# LARIX_V2.net
KiCad netlist of a schematic drawn in EAGLE
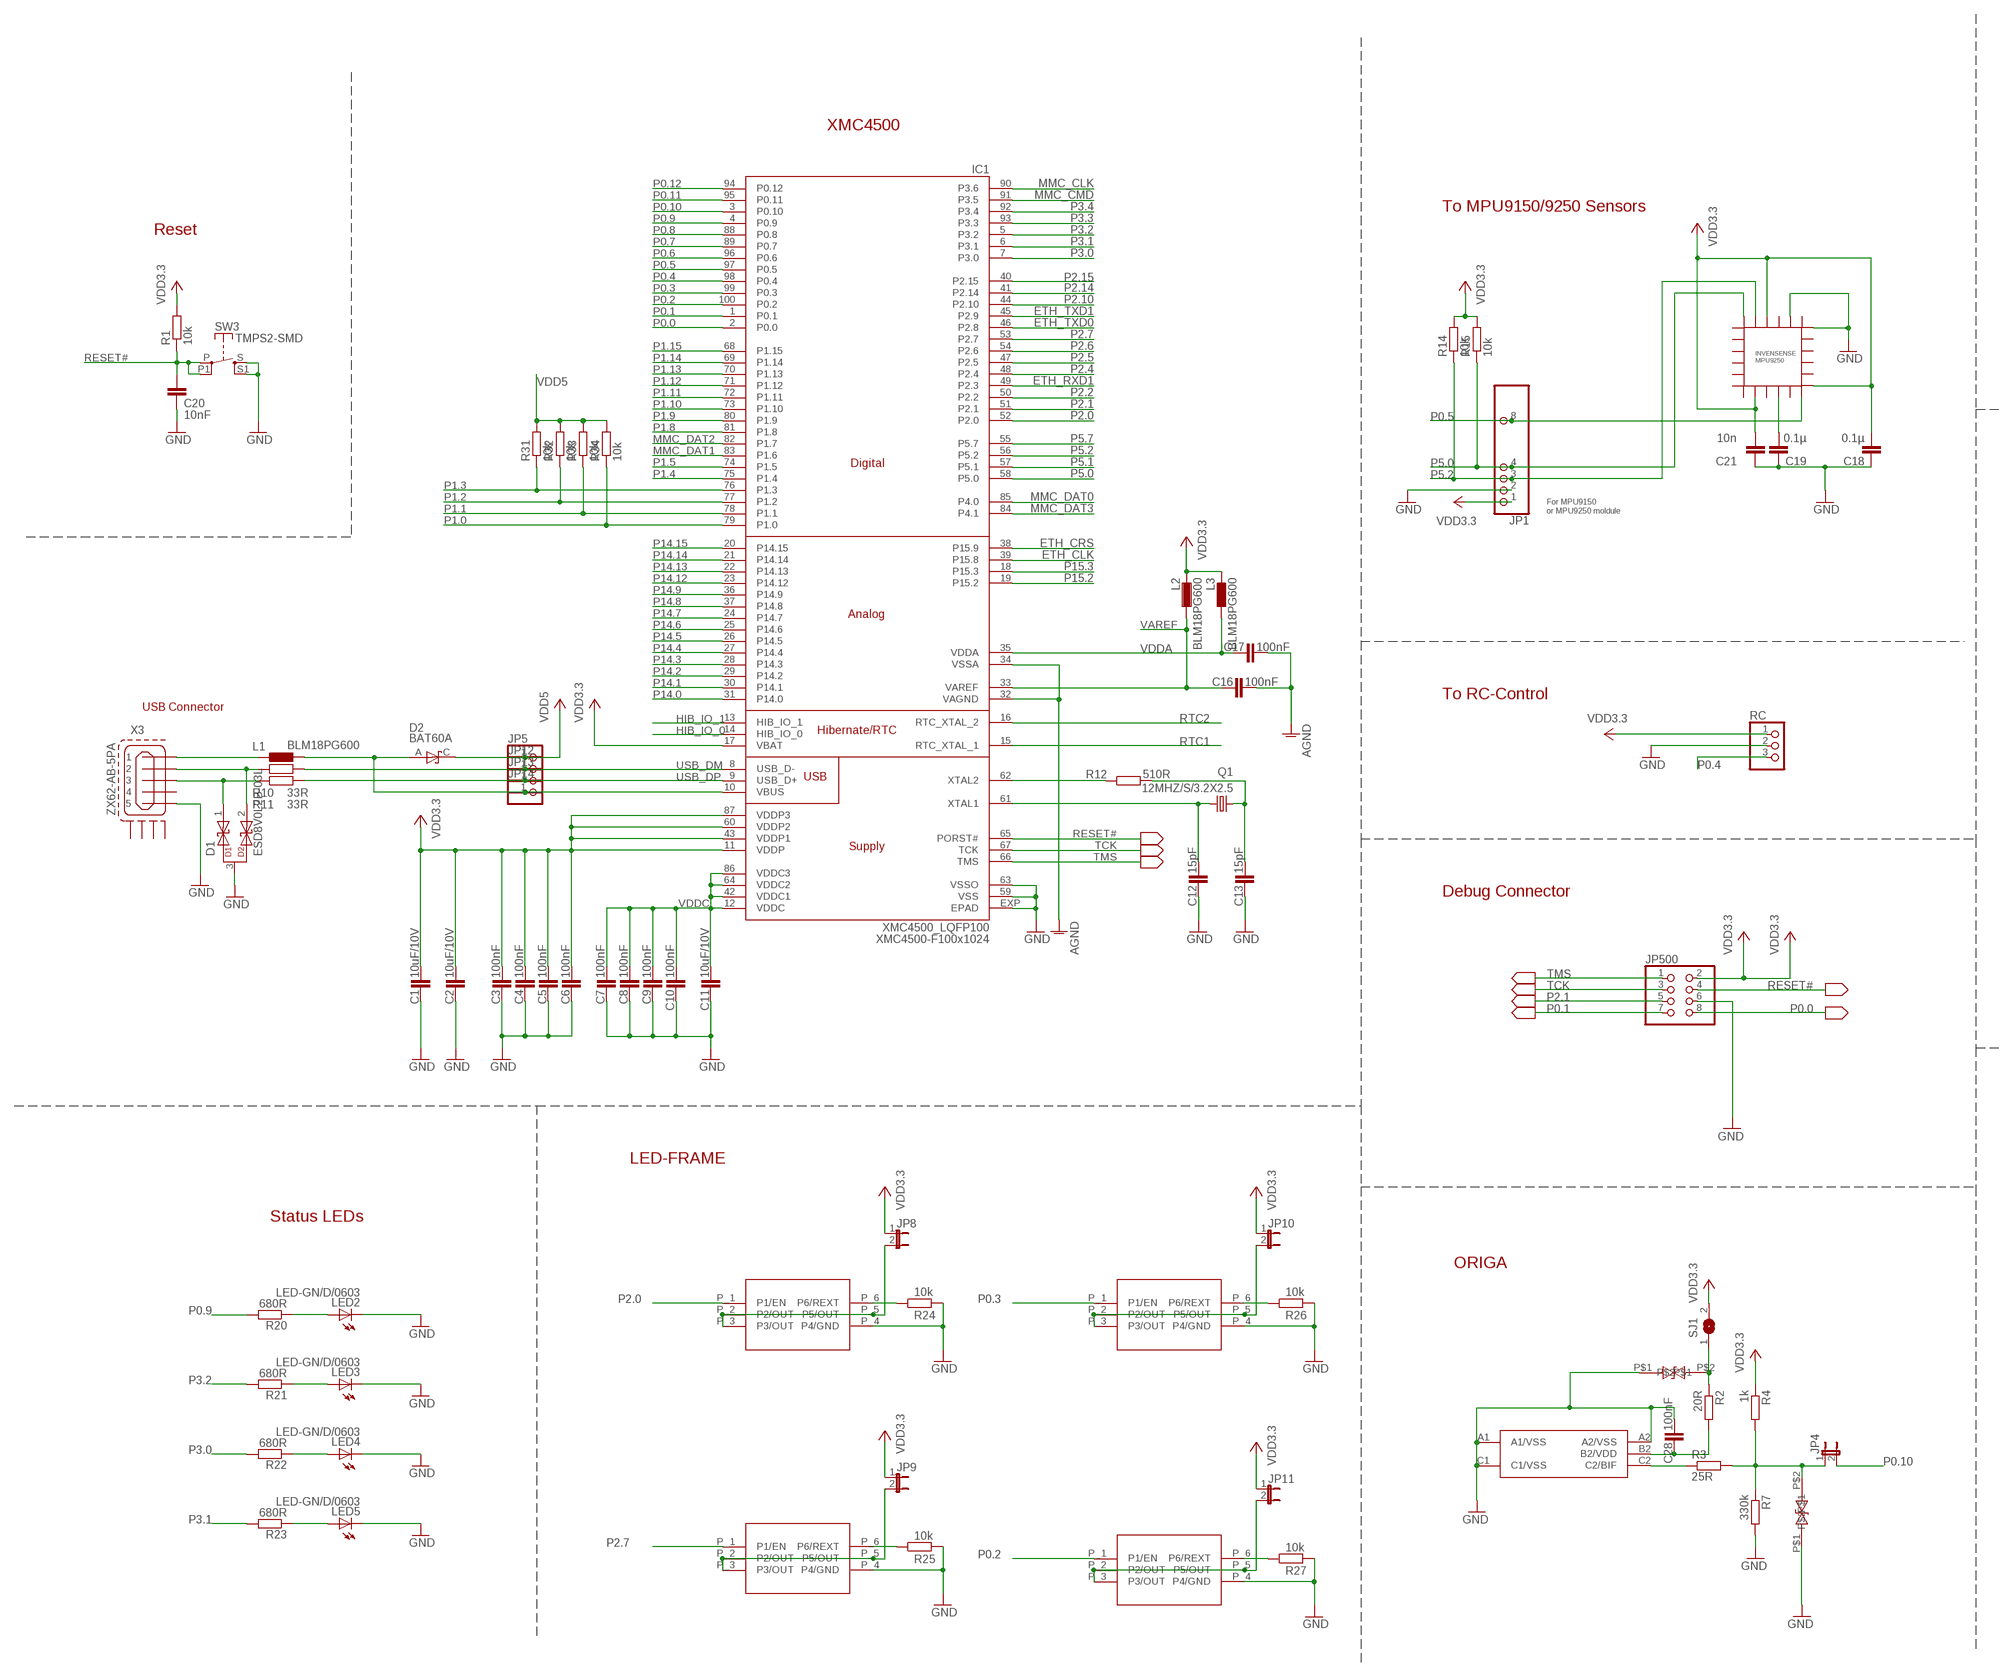
[diagram p0: schematic, sheet 1, part 1 of 2]
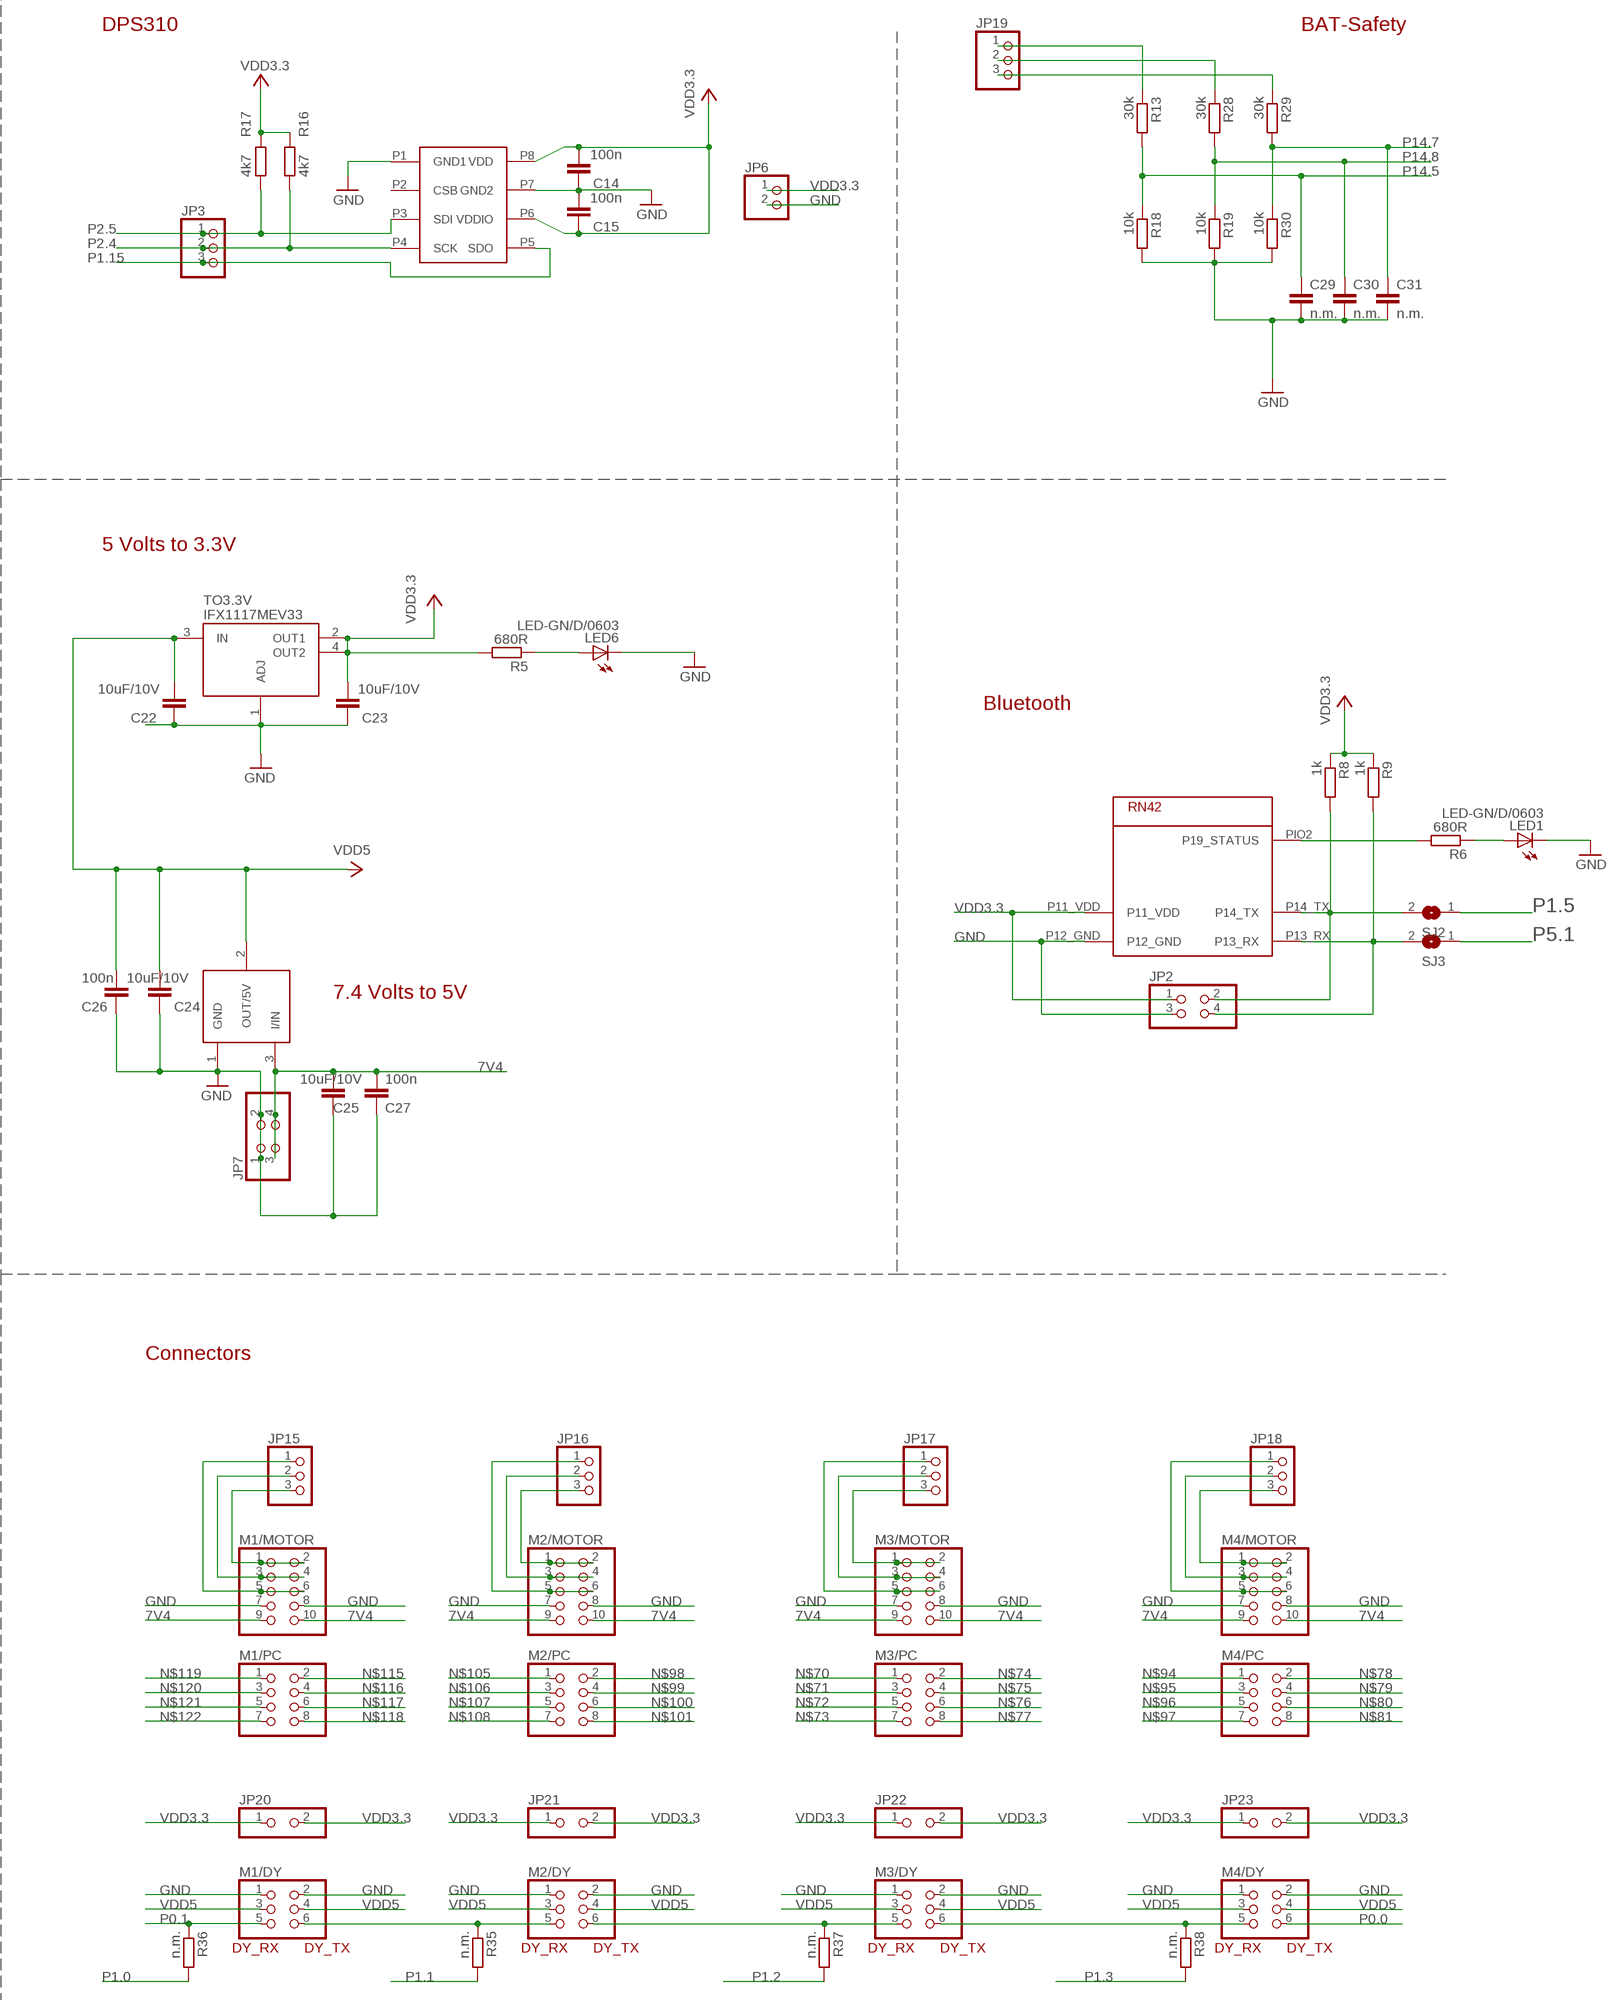
[diagram p1: schematic, sheet 1, part 2 of 2]

(export (version "E")
  (design (tool "Eeschema 10.0.6"))
  (components
    (comp (ref "C1")
      (value "10uF/10V")
      (footprint "eagle-import:C0805K")
      (libsource (lib "eagle-import") (part "C-EUC0805K"))
    )
    (comp (ref "C2")
      (value "10uF/10V")
      (footprint "eagle-import:C0805K")
      (libsource (lib "eagle-import") (part "C-EUC0805K"))
    )
    (comp (ref "C3")
      (value "100nF")
      (footprint "eagle-import:C0603")
      (libsource (lib "eagle-import") (part "resistor_C-EUC0603"))
    )
    (comp (ref "C4")
      (value "100nF")
      (footprint "eagle-import:C0603")
      (libsource (lib "eagle-import") (part "resistor_C-EUC0603"))
    )
    (comp (ref "C5")
      (value "100nF")
      (footprint "eagle-import:C0603")
      (libsource (lib "eagle-import") (part "resistor_C-EUC0603"))
    )
    (comp (ref "C6")
      (value "100nF")
      (footprint "eagle-import:C0603")
      (libsource (lib "eagle-import") (part "resistor_C-EUC0603"))
    )
    (comp (ref "C7")
      (value "100nF")
      (footprint "eagle-import:C0603")
      (libsource (lib "eagle-import") (part "resistor_C-EUC0603"))
    )
    (comp (ref "C8")
      (value "100nF")
      (footprint "eagle-import:C0603")
      (libsource (lib "eagle-import") (part "resistor_C-EUC0603"))
    )
    (comp (ref "C9")
      (value "100nF")
      (footprint "eagle-import:C0603")
      (libsource (lib "eagle-import") (part "resistor_C-EUC0603"))
    )
    (comp (ref "C10")
      (value "100nF")
      (footprint "eagle-import:C0603")
      (libsource (lib "eagle-import") (part "resistor_C-EUC0603"))
    )
    (comp (ref "C11")
      (value "10uF/10V")
      (footprint "eagle-import:C0805K")
      (libsource (lib "eagle-import") (part "C-EUC0805K"))
    )
    (comp (ref "C12")
      (value "15pF")
      (footprint "eagle-import:C0603")
      (libsource (lib "eagle-import") (part "resistor_C-EUC0603"))
    )
    (comp (ref "C13")
      (value "15pF")
      (footprint "eagle-import:C0603")
      (libsource (lib "eagle-import") (part "resistor_C-EUC0603"))
    )
    (comp (ref "C14")
      (value "100n")
      (footprint "eagle-import:C0603")
      (libsource (lib "eagle-import") (part "resistor_C-EUC0603"))
    )
    (comp (ref "C15")
      (value "100n")
      (footprint "eagle-import:C0603")
      (libsource (lib "eagle-import") (part "resistor_C-EUC0603"))
    )
    (comp (ref "C16")
      (value "100nF")
      (footprint "eagle-import:C0603")
      (libsource (lib "eagle-import") (part "resistor_C-EUC0603"))
    )
    (comp (ref "C17")
      (value "100nF")
      (footprint "eagle-import:C0603")
      (libsource (lib "eagle-import") (part "resistor_C-EUC0603"))
    )
    (comp (ref "C18")
      (value "0.1µ")
      (footprint "eagle-import:C0603")
      (libsource (lib "eagle-import") (part "resistor_C-EUC0603"))
    )
    (comp (ref "C19")
      (value "0.1µ")
      (footprint "eagle-import:C0603")
      (libsource (lib "eagle-import") (part "resistor_C-EUC0603"))
    )
    (comp (ref "C20")
      (value "10nF")
      (footprint "eagle-import:C0603")
      (libsource (lib "eagle-import") (part "resistor_C-EUC0603"))
    )
    (comp (ref "C21")
      (value "10n")
      (footprint "eagle-import:C0603")
      (libsource (lib "eagle-import") (part "resistor_C-EUC0603"))
    )
    (comp (ref "C22")
      (value "10uF/10V")
      (footprint "eagle-import:C0805K")
      (libsource (lib "eagle-import") (part "C-EUC0805K"))
    )
    (comp (ref "C23")
      (value "10uF/10V")
      (footprint "eagle-import:C0805K")
      (libsource (lib "eagle-import") (part "C-EUC0805K"))
    )
    (comp (ref "C24")
      (value "10uF/10V")
      (footprint "eagle-import:C0805K")
      (libsource (lib "eagle-import") (part "C-EUC0805K"))
    )
    (comp (ref "C25")
      (value "10uF/10V")
      (footprint "eagle-import:C0805K")
      (libsource (lib "eagle-import") (part "C-EUC0805K"))
    )
    (comp (ref "C26")
      (value "100n")
      (footprint "eagle-import:C0603")
      (libsource (lib "eagle-import") (part "resistor_C-EUC0603"))
    )
    (comp (ref "C27")
      (value "100n")
      (footprint "eagle-import:C0603")
      (libsource (lib "eagle-import") (part "resistor_C-EUC0603"))
    )
    (comp (ref "C28")
      (value "100nF")
      (footprint "eagle-import:C0603")
      (libsource (lib "eagle-import") (part "resistor_C-EUC0603"))
    )
    (comp (ref "C29")
      (value "n.m.")
      (footprint "eagle-import:C0603")
      (libsource (lib "eagle-import") (part "resistor_C-EUC0603"))
    )
    (comp (ref "C30")
      (value "n.m.")
      (footprint "eagle-import:C0603")
      (libsource (lib "eagle-import") (part "resistor_C-EUC0603"))
    )
    (comp (ref "C31")
      (value "n.m.")
      (footprint "eagle-import:C0603")
      (libsource (lib "eagle-import") (part "resistor_C-EUC0603"))
    )
    (comp (ref "D1")
      (value "ESD8V0L2B-03L")
      (footprint "eagle-import:TSLP-3-1")
      (libsource (lib "eagle-import") (part "ESD8V0L2B-03L"))
    )
    (comp (ref "D2")
      (value "BAT60A")
      (footprint "eagle-import:SOD323-R")
      (libsource (lib "eagle-import") (part "BAT60"))
    )
    (comp (ref "IC1")
      (value "XMC4500_LQFP100")
      (footprint "eagle-import:P_PG-LQFP-100-11")
      (libsource (lib "eagle-import") (part "XMC4400_LQFP100"))
    )
    (comp (ref "IC2")
      (value "INVENSENSE9250EHERBY")
      (footprint "eagle-import:QFN3X3-24+")
      (libsource (lib "eagle-import") (part "INVENSENSE9250HERBYE"))
    )
    (comp (ref "JP1")
      (value "PINHD-1X10")
      (footprint "eagle-import:1X10")
      (libsource (lib "eagle-import") (part "PINHD-1X10"))
    )
    (comp (ref "JP2")
      (value "PINHD-2X2")
      (footprint "eagle-import:2X02")
      (libsource (lib "eagle-import") (part "PINHD-2X2"))
    )
    (comp (ref "JP3")
      (value "PINHD-1X3")
      (footprint "eagle-import:1X03")
      (libsource (lib "eagle-import") (part "PINHD-1X3"))
    )
    (comp (ref "JP4")
      (value "JP1E")
      (footprint "eagle-import:JP1")
      (libsource (lib "eagle-import") (part "JP1E"))
    )
    (comp (ref "JP5")
      (value "PINHD-1X1")
      (footprint "eagle-import:1X01")
      (libsource (lib "eagle-import") (part "PINHD-1X1"))
    )
    (comp (ref "JP6")
      (value "PINHD-1X2")
      (footprint "eagle-import:1X02")
      (libsource (lib "eagle-import") (part "PINHD-1X2"))
    )
    (comp (ref "JP7")
      (value "PINHD-2X2")
      (footprint "eagle-import:2X02")
      (libsource (lib "eagle-import") (part "PINHD-2X2"))
    )
    (comp (ref "JP8")
      (value "JP1E")
      (footprint "eagle-import:JP1")
      (libsource (lib "eagle-import") (part "JP1E"))
    )
    (comp (ref "JP9")
      (value "JP1E")
      (footprint "eagle-import:JP1")
      (libsource (lib "eagle-import") (part "JP1E"))
    )
    (comp (ref "JP10")
      (value "JP1E")
      (footprint "eagle-import:JP1")
      (libsource (lib "eagle-import") (part "JP1E"))
    )
    (comp (ref "JP11")
      (value "JP1E")
      (footprint "eagle-import:JP1")
      (libsource (lib "eagle-import") (part "JP1E"))
    )
    (comp (ref "JP12")
      (value "PINHD-1X1")
      (footprint "eagle-import:1X01")
      (libsource (lib "eagle-import") (part "PINHD-1X1"))
    )
    (comp (ref "JP13")
      (value "PINHD-1X1")
      (footprint "eagle-import:1X01")
      (libsource (lib "eagle-import") (part "PINHD-1X1"))
    )
    (comp (ref "JP14")
      (value "PINHD-1X1")
      (footprint "eagle-import:1X01")
      (libsource (lib "eagle-import") (part "PINHD-1X1"))
    )
    (comp (ref "JP15")
      (value "PINHD-1X3")
      (footprint "eagle-import:1X03")
      (libsource (lib "eagle-import") (part "PINHD-1X3"))
    )
    (comp (ref "JP16")
      (value "PINHD-1X3")
      (footprint "eagle-import:1X03")
      (libsource (lib "eagle-import") (part "PINHD-1X3"))
    )
    (comp (ref "JP17")
      (value "PINHD-1X3")
      (footprint "eagle-import:1X03")
      (libsource (lib "eagle-import") (part "PINHD-1X3"))
    )
    (comp (ref "JP18")
      (value "PINHD-1X3")
      (footprint "eagle-import:1X03")
      (libsource (lib "eagle-import") (part "PINHD-1X3"))
    )
    (comp (ref "JP19")
      (value "PINHD-1X3")
      (footprint "eagle-import:1X03")
      (libsource (lib "eagle-import") (part "PINHD-1X3"))
    )
    (comp (ref "JP20")
      (value "PINHD-2X3")
      (footprint "eagle-import:2X03")
      (libsource (lib "eagle-import") (part "pinhead_2we_PINHD-2X3"))
    )
    (comp (ref "JP21")
      (value "PINHD-2X3")
      (footprint "eagle-import:2X03")
      (libsource (lib "eagle-import") (part "pinhead_2we_PINHD-2X3"))
    )
    (comp (ref "JP22")
      (value "PINHD-2X3")
      (footprint "eagle-import:2X03")
      (libsource (lib "eagle-import") (part "pinhead_2we_PINHD-2X3"))
    )
    (comp (ref "JP23")
      (value "PINHD-2X3")
      (footprint "eagle-import:2X03")
      (libsource (lib "eagle-import") (part "pinhead_2we_PINHD-2X3"))
    )
    (comp (ref "JP500")
      (value "PINHD-2X4")
      (footprint "eagle-import:2X04")
      (libsource (lib "eagle-import") (part "PINHD-2X4"))
    )
    (comp (ref "L1")
      (value "BLM18PG600")
      (footprint "eagle-import:L1608")
      (libsource (lib "eagle-import") (part "L_EU_L0603"))
    )
    (comp (ref "L2")
      (value "BLM18PG600")
      (footprint "eagle-import:L1608")
      (libsource (lib "eagle-import") (part "L_EU_L0603"))
    )
    (comp (ref "L3")
      (value "BLM18PG600")
      (footprint "eagle-import:L1608")
      (libsource (lib "eagle-import") (part "L_EU_L0603"))
    )
    (comp (ref "LED1")
      (value "LED-GN/D/0603")
      (footprint "eagle-import:CHIPLED_0603")
      (libsource (lib "eagle-import") (part "LEDCHIPLED_0603"))
    )
    (comp (ref "LED2")
      (value "LED-GN/D/0603")
      (footprint "eagle-import:CHIPLED_0603")
      (libsource (lib "eagle-import") (part "LEDCHIPLED_0603"))
    )
    (comp (ref "LED3")
      (value "LED-GN/D/0603")
      (footprint "eagle-import:CHIPLED_0603")
      (libsource (lib "eagle-import") (part "LEDCHIPLED_0603"))
    )
    (comp (ref "LED4")
      (value "LED-GN/D/0603")
      (footprint "eagle-import:CHIPLED_0603")
      (libsource (lib "eagle-import") (part "LEDCHIPLED_0603"))
    )
    (comp (ref "LED5")
      (value "LED-GN/D/0603")
      (footprint "eagle-import:CHIPLED_0603")
      (libsource (lib "eagle-import") (part "LEDCHIPLED_0603"))
    )
    (comp (ref "LED6")
      (value "LED-GN/D/0603")
      (footprint "eagle-import:CHIPLED_0603")
      (libsource (lib "eagle-import") (part "LEDCHIPLED_0603"))
    )
    (comp (ref "M1/DY")
      (value "PINHD-2X3")
      (footprint "eagle-import:2X03")
      (libsource (lib "eagle-import") (part "PINHD-2X3"))
    )
    (comp (ref "M1/MOTOR")
      (value "PINHD-2X5")
      (footprint "eagle-import:2X05")
      (libsource (lib "eagle-import") (part "PINHD-2X5"))
    )
    (comp (ref "M1/PC")
      (value "PINHD-2X4")
      (footprint "eagle-import:2X04")
      (libsource (lib "eagle-import") (part "PINHD-2X4"))
    )
    (comp (ref "M2/DY")
      (value "PINHD-2X3")
      (footprint "eagle-import:2X03")
      (libsource (lib "eagle-import") (part "PINHD-2X3"))
    )
    (comp (ref "M2/MOTOR")
      (value "PINHD-2X5")
      (footprint "eagle-import:2X05")
      (libsource (lib "eagle-import") (part "PINHD-2X5"))
    )
    (comp (ref "M2/PC")
      (value "PINHD-2X4")
      (footprint "eagle-import:2X04")
      (libsource (lib "eagle-import") (part "PINHD-2X4"))
    )
    (comp (ref "M3/DY")
      (value "PINHD-2X3")
      (footprint "eagle-import:2X03")
      (libsource (lib "eagle-import") (part "PINHD-2X3"))
    )
    (comp (ref "M3/MOTOR")
      (value "PINHD-2X5")
      (footprint "eagle-import:2X05")
      (libsource (lib "eagle-import") (part "PINHD-2X5"))
    )
    (comp (ref "M3/PC")
      (value "PINHD-2X4")
      (footprint "eagle-import:2X04")
      (libsource (lib "eagle-import") (part "PINHD-2X4"))
    )
    (comp (ref "M4/DY")
      (value "PINHD-2X3")
      (footprint "eagle-import:2X03")
      (libsource (lib "eagle-import") (part "PINHD-2X3"))
    )
    (comp (ref "M4/MOTOR")
      (value "PINHD-2X5")
      (footprint "eagle-import:2X05")
      (libsource (lib "eagle-import") (part "PINHD-2X5"))
    )
    (comp (ref "M4/PC")
      (value "PINHD-2X4")
      (footprint "eagle-import:2X04")
      (libsource (lib "eagle-import") (part "PINHD-2X4"))
    )
    (comp (ref "Q1")
      (value "12MHZ/S/3.2X2.5")
      (footprint "eagle-import:32X25_4PAD")
      (libsource (lib "eagle-import") (part "NX3225_2"))
    )
    (comp (ref "R1")
      (value "10k")
      (footprint "eagle-import:R0603")
      (libsource (lib "eagle-import") (part "resistor_R-EU_R0603"))
    )
    (comp (ref "R2")
      (value "20R")
      (footprint "eagle-import:R0603")
      (libsource (lib "eagle-import") (part "R-EU_R0603"))
    )
    (comp (ref "R3")
      (value "25R")
      (footprint "eagle-import:R0603")
      (libsource (lib "eagle-import") (part "R-EU_R0603"))
    )
    (comp (ref "R4")
      (value "1k")
      (footprint "eagle-import:R0603")
      (libsource (lib "eagle-import") (part "R-EU_R0603"))
    )
    (comp (ref "R5")
      (value "680R")
      (footprint "eagle-import:R0603")
      (libsource (lib "eagle-import") (part "R-EU_R0603"))
    )
    (comp (ref "R6")
      (value "680R")
      (footprint "eagle-import:R0603")
      (libsource (lib "eagle-import") (part "R-EU_R0603"))
    )
    (comp (ref "R7")
      (value "330k")
      (footprint "eagle-import:R0603")
      (libsource (lib "eagle-import") (part "R-EU_R0603"))
    )
    (comp (ref "R8")
      (value "1k")
      (footprint "eagle-import:R0603")
      (libsource (lib "eagle-import") (part "R-EU_R0603"))
    )
    (comp (ref "R9")
      (value "1k")
      (footprint "eagle-import:R0603")
      (libsource (lib "eagle-import") (part "R-EU_R0603"))
    )
    (comp (ref "R10")
      (value "33R")
      (footprint "eagle-import:R0603")
      (libsource (lib "eagle-import") (part "resistor_R-EU_R0603"))
    )
    (comp (ref "R11")
      (value "33R")
      (footprint "eagle-import:R0603")
      (libsource (lib "eagle-import") (part "resistor_R-EU_R0603"))
    )
    (comp (ref "R12")
      (value "510R")
      (footprint "eagle-import:R0603")
      (libsource (lib "eagle-import") (part "R-EU_R0603"))
    )
    (comp (ref "R13")
      (value "30k")
      (footprint "eagle-import:R0603")
      (libsource (lib "eagle-import") (part "R-EU_R0603"))
    )
    (comp (ref "R14")
      (value "10k")
      (footprint "eagle-import:R0603")
      (libsource (lib "eagle-import") (part "resistor_R-EU_R0603"))
    )
    (comp (ref "R15")
      (value "10k")
      (footprint "eagle-import:R0603")
      (libsource (lib "eagle-import") (part "resistor_R-EU_R0603"))
    )
    (comp (ref "R16")
      (value "4k7")
      (footprint "eagle-import:R0603")
      (libsource (lib "eagle-import") (part "resistor_R-EU_R0603"))
    )
    (comp (ref "R17")
      (value "4k7")
      (footprint "eagle-import:R0603")
      (libsource (lib "eagle-import") (part "resistor_R-EU_R0603"))
    )
    (comp (ref "R18")
      (value "10k")
      (footprint "eagle-import:R0603")
      (libsource (lib "eagle-import") (part "R-EU_R0603"))
    )
    (comp (ref "R19")
      (value "10k")
      (footprint "eagle-import:R0603")
      (libsource (lib "eagle-import") (part "R-EU_R0603"))
    )
    (comp (ref "R20")
      (value "680R")
      (footprint "eagle-import:R0603")
      (libsource (lib "eagle-import") (part "R-EU_R0603"))
    )
    (comp (ref "R21")
      (value "680R")
      (footprint "eagle-import:R0603")
      (libsource (lib "eagle-import") (part "R-EU_R0603"))
    )
    (comp (ref "R22")
      (value "680R")
      (footprint "eagle-import:R0603")
      (libsource (lib "eagle-import") (part "R-EU_R0603"))
    )
    (comp (ref "R23")
      (value "680R")
      (footprint "eagle-import:R0603")
      (libsource (lib "eagle-import") (part "R-EU_R0603"))
    )
    (comp (ref "R24")
      (value "10k")
      (footprint "eagle-import:R0603")
      (libsource (lib "eagle-import") (part "resistor_R-EU_R0603"))
    )
    (comp (ref "R25")
      (value "10k")
      (footprint "eagle-import:R0603")
      (libsource (lib "eagle-import") (part "resistor_R-EU_R0603"))
    )
    (comp (ref "R26")
      (value "10k")
      (footprint "eagle-import:R0603")
      (libsource (lib "eagle-import") (part "resistor_R-EU_R0603"))
    )
    (comp (ref "R27")
      (value "10k")
      (footprint "eagle-import:R0603")
      (libsource (lib "eagle-import") (part "resistor_R-EU_R0603"))
    )
    (comp (ref "R28")
      (value "30k")
      (footprint "eagle-import:R0603")
      (libsource (lib "eagle-import") (part "R-EU_R0603"))
    )
    (comp (ref "R29")
      (value "30k")
      (footprint "eagle-import:R0603")
      (libsource (lib "eagle-import") (part "R-EU_R0603"))
    )
    (comp (ref "R30")
      (value "10k")
      (footprint "eagle-import:R0603")
      (libsource (lib "eagle-import") (part "R-EU_R0603"))
    )
    (comp (ref "R31")
      (value "10k")
      (footprint "eagle-import:R0603")
      (libsource (lib "eagle-import") (part "resistor_R-EU_R0603"))
    )
    (comp (ref "R32")
      (value "10k")
      (footprint "eagle-import:R0603")
      (libsource (lib "eagle-import") (part "resistor_R-EU_R0603"))
    )
    (comp (ref "R33")
      (value "10k")
      (footprint "eagle-import:R0603")
      (libsource (lib "eagle-import") (part "resistor_R-EU_R0603"))
    )
    (comp (ref "R34")
      (value "10k")
      (footprint "eagle-import:R0603")
      (libsource (lib "eagle-import") (part "resistor_R-EU_R0603"))
    )
    (comp (ref "R35")
      (value "n.m.")
      (footprint "eagle-import:R0603")
      (libsource (lib "eagle-import") (part "R-EU_R0603"))
    )
    (comp (ref "R36")
      (value "n.m.")
      (footprint "eagle-import:R0603")
      (libsource (lib "eagle-import") (part "R-EU_R0603"))
    )
    (comp (ref "R37")
      (value "n.m.")
      (footprint "eagle-import:R0603")
      (libsource (lib "eagle-import") (part "R-EU_R0603"))
    )
    (comp (ref "R38")
      (value "n.m.")
      (footprint "eagle-import:R0603")
      (libsource (lib "eagle-import") (part "R-EU_R0603"))
    )
    (comp (ref "RC")
      (value "PINHD-1X3")
      (footprint "eagle-import:1X03")
      (libsource (lib "eagle-import") (part "PINHD-1X3"))
    )
    (comp (ref "SJ1") (value "SJ") (footprint "eagle-import:SJ") (libsource (lib "eagle-import") (part "SJ")))
    (comp (ref "SJ2") (value "SJ") (footprint "eagle-import:SJ") (libsource (lib "eagle-import") (part "SJ")))
    (comp (ref "SJ3") (value "SJ") (footprint "eagle-import:SJ") (libsource (lib "eagle-import") (part "SJ")))
    (comp (ref "SW3")
      (value "TMPS2-SMD")
      (footprint "eagle-import:FSM2JSMA")
      (libsource (lib "eagle-import") (part "FSM2JSMA"))
    )
    (comp (ref "TO3.3V")
      (value "IFX1117MEV33")
      (footprint "eagle-import:SOT223")
      (libsource (lib "eagle-import") (part "IFX1117"))
    )
    (comp (ref "U$7")
      (value "TLE4284V50")
      (footprint "eagle-import:INF-PG-TO252-3-1_L_1PRIMARY")
      (libsource (lib "eagle-import") (part "TLE4284V50"))
    )
    (comp (ref "U$8")
      (value "DPS310DRUCKSENSOR")
      (footprint "eagle-import:LGA8R125P0X4_500X300X120")
      (libsource (lib "eagle-import") (part "DPS310DRUCKSENSOR"))
    )
    (comp (ref "U$9")
      (value "ESD218-B1-02EL")
      (footprint "eagle-import:TSLP-2-20")
      (libsource (lib "eagle-import") (part "ESD218-B1-02EL"))
    )
    (comp (ref "U$11")
      (value "ORIGA2L")
      (footprint "eagle-import:WLB-5")
      (libsource (lib "eagle-import") (part "ORIGA2L"))
    )
    (comp (ref "U$13")
      (value "BCU320")
      (footprint "eagle-import:SC74")
      (libsource (lib "eagle-import") (part "BCU320"))
    )
    (comp (ref "U$15")
      (value "BCU320")
      (footprint "eagle-import:SC74")
      (libsource (lib "eagle-import") (part "BCU320"))
    )
    (comp (ref "U$16")
      (value "BLUETOOTHRN42")
      (footprint "eagle-import:ROVING-SHORT")
      (libsource (lib "eagle-import") (part "BLUETOOTHRN42"))
    )
    (comp (ref "U$18")
      (value "BCU320")
      (footprint "eagle-import:SC74")
      (libsource (lib "eagle-import") (part "BCU320"))
    )
    (comp (ref "U$20")
      (value "BCU320")
      (footprint "eagle-import:SC74")
      (libsource (lib "eagle-import") (part "BCU320"))
    )
    (comp (ref "U$22")
      (value "ESD218-B1-02EL")
      (footprint "eagle-import:TSLP-2-20")
      (libsource (lib "eagle-import") (part "ESD218-B1-02EL"))
    )
    (comp (ref "X3")
      (value "ZX62-AB-5PA")
      (footprint "eagle-import:ZX62-AB-5PA_MICRO-USB")
      (libsource (lib "eagle-import") (part "ZX62-AB-5PA_MICRO-USB"))
    )
  )
  (nets
    (net (code "1") (name "/7V4") (class "Default")
      (node (ref "C25") (pin "1") (pinfunction "1_1") (pintype "passive"))
      (node (ref "C27") (pin "1") (pinfunction "1_1") (pintype "passive"))
      (node (ref "JP7") (pin "3") (pinfunction "3_3") (pintype "passive"))
      (node (ref "JP7") (pin "4") (pinfunction "4_4") (pintype "passive"))
      (node (ref "M1/MOTOR") (pin "10") (pinfunction "10_10") (pintype "passive"))
      (node (ref "M1/MOTOR") (pin "9") (pinfunction "9_9") (pintype "passive"))
      (node (ref "M2/MOTOR") (pin "10") (pinfunction "10_10") (pintype "passive"))
      (node (ref "M2/MOTOR") (pin "9") (pinfunction "9_9") (pintype "passive"))
      (node (ref "M3/MOTOR") (pin "10") (pinfunction "10_10") (pintype "passive"))
      (node (ref "M3/MOTOR") (pin "9") (pinfunction "9_9") (pintype "passive"))
      (node (ref "M4/MOTOR") (pin "10") (pinfunction "10_10") (pintype "passive"))
      (node (ref "M4/MOTOR") (pin "9") (pinfunction "9_9") (pintype "passive"))
      (node (ref "U$7") (pin "3") (pinfunction "I/IN_3") (pintype "bidirectional"))
    )
    (net (code "2") (name "/ETH_CLK") (class "Default")
      (node (ref "IC1") (pin "39") (pinfunction "P15.8_39") (pintype "bidirectional"))
    )
    (net (code "3") (name "/ETH_CRS") (class "Default")
      (node (ref "IC1") (pin "38") (pinfunction "P15.9_38") (pintype "bidirectional"))
    )
    (net (code "4") (name "/ETH_RXD1") (class "Default")
      (node (ref "IC1") (pin "49") (pinfunction "P2.3_49") (pintype "bidirectional"))
    )
    (net (code "5") (name "/ETH_TXD0") (class "Default")
      (node (ref "IC1") (pin "46") (pinfunction "P2.8_46") (pintype "bidirectional"))
    )
    (net (code "6") (name "/ETH_TXD1") (class "Default")
      (node (ref "IC1") (pin "45") (pinfunction "P2.9_45") (pintype "bidirectional"))
    )
    (net (code "7") (name "/HIB_IO_0") (class "Default")
      (node (ref "IC1") (pin "14") (pinfunction "HIB_IO_0_14") (pintype "bidirectional"))
    )
    (net (code "8") (name "/HIB_IO_1") (class "Default")
      (node (ref "IC1") (pin "13") (pinfunction "HIB_IO_1_13") (pintype "bidirectional"))
    )
    (net (code "9") (name "/MMC_CLK") (class "Default")
      (node (ref "IC1") (pin "90") (pinfunction "P3.6_90") (pintype "bidirectional"))
    )
    (net (code "10") (name "/MMC_CMD") (class "Default")
      (node (ref "IC1") (pin "91") (pinfunction "P3.5_91") (pintype "bidirectional"))
    )
    (net (code "11") (name "/MMC_DAT0") (class "Default")
      (node (ref "IC1") (pin "85") (pinfunction "P4.0_85") (pintype "bidirectional"))
    )
    (net (code "12") (name "/MMC_DAT1") (class "Default")
      (node (ref "IC1") (pin "83") (pinfunction "P1.6_83") (pintype "bidirectional"))
    )
    (net (code "13") (name "/MMC_DAT2") (class "Default")
      (node (ref "IC1") (pin "82") (pinfunction "P1.7_82") (pintype "bidirectional"))
    )
    (net (code "14") (name "/MMC_DAT3") (class "Default")
      (node (ref "IC1") (pin "84") (pinfunction "P4.1_84") (pintype "bidirectional"))
    )
    (net (code "15") (name "/N$70") (class "Default")
      (node (ref "M3/PC") (pin "1") (pinfunction "1_1") (pintype "passive"))
    )
    (net (code "16") (name "/N$71") (class "Default")
      (node (ref "M3/PC") (pin "3") (pinfunction "3_3") (pintype "passive"))
    )
    (net (code "17") (name "/N$72") (class "Default")
      (node (ref "M3/PC") (pin "5") (pinfunction "5_5") (pintype "passive"))
    )
    (net (code "18") (name "/N$73") (class "Default")
      (node (ref "M3/PC") (pin "7") (pinfunction "7_7") (pintype "passive"))
    )
    (net (code "19") (name "/N$74") (class "Default")
      (node (ref "M3/PC") (pin "2") (pinfunction "2_2") (pintype "passive"))
    )
    (net (code "20") (name "/N$75") (class "Default")
      (node (ref "M3/PC") (pin "4") (pinfunction "4_4") (pintype "passive"))
    )
    (net (code "21") (name "/N$76") (class "Default")
      (node (ref "M3/PC") (pin "6") (pinfunction "6_6") (pintype "passive"))
    )
    (net (code "22") (name "/N$77") (class "Default")
      (node (ref "M3/PC") (pin "8") (pinfunction "8_8") (pintype "passive"))
    )
    (net (code "23") (name "/N$78") (class "Default")
      (node (ref "M4/PC") (pin "2") (pinfunction "2_2") (pintype "passive"))
    )
    (net (code "24") (name "/N$79") (class "Default")
      (node (ref "M4/PC") (pin "4") (pinfunction "4_4") (pintype "passive"))
    )
    (net (code "25") (name "/N$80") (class "Default")
      (node (ref "M4/PC") (pin "6") (pinfunction "6_6") (pintype "passive"))
    )
    (net (code "26") (name "/N$81") (class "Default")
      (node (ref "M4/PC") (pin "8") (pinfunction "8_8") (pintype "passive"))
    )
    (net (code "27") (name "/N$94") (class "Default")
      (node (ref "M4/PC") (pin "1") (pinfunction "1_1") (pintype "passive"))
    )
    (net (code "28") (name "/N$95") (class "Default")
      (node (ref "M4/PC") (pin "3") (pinfunction "3_3") (pintype "passive"))
    )
    (net (code "29") (name "/N$96") (class "Default")
      (node (ref "M4/PC") (pin "5") (pinfunction "5_5") (pintype "passive"))
    )
    (net (code "30") (name "/N$97") (class "Default")
      (node (ref "M4/PC") (pin "7") (pinfunction "7_7") (pintype "passive"))
    )
    (net (code "31") (name "/N$98") (class "Default")
      (node (ref "M2/PC") (pin "2") (pinfunction "2_2") (pintype "passive"))
    )
    (net (code "32") (name "/N$99") (class "Default")
      (node (ref "M2/PC") (pin "4") (pinfunction "4_4") (pintype "passive"))
    )
    (net (code "33") (name "/N$100") (class "Default")
      (node (ref "M2/PC") (pin "6") (pinfunction "6_6") (pintype "passive"))
    )
    (net (code "34") (name "/N$101") (class "Default")
      (node (ref "M2/PC") (pin "8") (pinfunction "8_8") (pintype "passive"))
    )
    (net (code "35") (name "/N$105") (class "Default")
      (node (ref "M2/PC") (pin "1") (pinfunction "1_1") (pintype "passive"))
    )
    (net (code "36") (name "/N$106") (class "Default")
      (node (ref "M2/PC") (pin "3") (pinfunction "3_3") (pintype "passive"))
    )
    (net (code "37") (name "/N$107") (class "Default")
      (node (ref "M2/PC") (pin "5") (pinfunction "5_5") (pintype "passive"))
    )
    (net (code "38") (name "/N$108") (class "Default")
      (node (ref "M2/PC") (pin "7") (pinfunction "7_7") (pintype "passive"))
    )
    (net (code "39") (name "/N$115") (class "Default")
      (node (ref "M1/PC") (pin "2") (pinfunction "2_2") (pintype "passive"))
    )
    (net (code "40") (name "/N$116") (class "Default")
      (node (ref "M1/PC") (pin "4") (pinfunction "4_4") (pintype "passive"))
    )
    (net (code "41") (name "/N$117") (class "Default")
      (node (ref "M1/PC") (pin "6") (pinfunction "6_6") (pintype "passive"))
    )
    (net (code "42") (name "/N$118") (class "Default")
      (node (ref "M1/PC") (pin "8") (pinfunction "8_8") (pintype "passive"))
    )
    (net (code "43") (name "/N$119") (class "Default")
      (node (ref "M1/PC") (pin "1") (pinfunction "1_1") (pintype "passive"))
    )
    (net (code "44") (name "/N$120") (class "Default")
      (node (ref "M1/PC") (pin "3") (pinfunction "3_3") (pintype "passive"))
    )
    (net (code "45") (name "/N$121") (class "Default")
      (node (ref "M1/PC") (pin "5") (pinfunction "5_5") (pintype "passive"))
    )
    (net (code "46") (name "/N$122") (class "Default")
      (node (ref "M1/PC") (pin "7") (pinfunction "7_7") (pintype "passive"))
    )
    (net (code "47") (name "/P0.0") (class "Default")
      (node (ref "IC1") (pin "2") (pinfunction "P0.0_2") (pintype "bidirectional"))
      (node (ref "JP500") (pin "8") (pinfunction "8_8") (pintype "passive"))
      (node (ref "M4/DY") (pin "6") (pinfunction "6_6") (pintype "passive"))
    )
    (net (code "48") (name "/P0.1") (class "Default")
      (node (ref "IC1") (pin "1") (pinfunction "P0.1_1") (pintype "bidirectional"))
      (node (ref "JP500") (pin "7") (pinfunction "7_7") (pintype "passive"))
      (node (ref "M1/DY") (pin "5") (pinfunction "5_5") (pintype "passive"))
      (node (ref "R36") (pin "1") (pinfunction "1_1") (pintype "passive"))
    )
    (net (code "49") (name "/P0.2") (class "Default")
      (node (ref "IC1") (pin "100") (pinfunction "P0.2_100") (pintype "bidirectional"))
      (node (ref "U$20") (pin "P_1") (pinfunction "P1/EN_P_1") (pintype "bidirectional"))
    )
    (net (code "50") (name "/P0.3") (class "Default")
      (node (ref "IC1") (pin "99") (pinfunction "P0.3_99") (pintype "bidirectional"))
      (node (ref "U$18") (pin "P_1") (pinfunction "P1/EN_P_1") (pintype "bidirectional"))
    )
    (net (code "51") (name "/P0.4") (class "Default")
      (node (ref "IC1") (pin "98") (pinfunction "P0.4_98") (pintype "bidirectional"))
      (node (ref "RC") (pin "3") (pinfunction "3_3") (pintype "passive"))
    )
    (net (code "52") (name "/P0.5") (class "Default")
      (node (ref "IC1") (pin "97") (pinfunction "P0.5_97") (pintype "bidirectional"))
      (node (ref "IC2") (pin "12") (pinfunction "12_12") (pintype "bidirectional"))
      (node (ref "JP1") (pin "8") (pinfunction "8_8") (pintype "passive"))
    )
    (net (code "53") (name "/P0.6") (class "Default")
      (node (ref "IC1") (pin "96") (pinfunction "P0.6_96") (pintype "bidirectional"))
    )
    (net (code "54") (name "/P0.7") (class "Default")
      (node (ref "IC1") (pin "89") (pinfunction "P0.7_89") (pintype "bidirectional"))
    )
    (net (code "55") (name "/P0.8") (class "Default")
      (node (ref "IC1") (pin "88") (pinfunction "P0.8_88") (pintype "bidirectional"))
    )
    (net (code "56") (name "/P0.9") (class "Default")
      (node (ref "IC1") (pin "4") (pinfunction "P0.9_4") (pintype "bidirectional"))
      (node (ref "R20") (pin "2") (pinfunction "2_2") (pintype "passive"))
    )
    (net (code "57") (name "/P0.10") (class "Default")
      (node (ref "IC1") (pin "3") (pinfunction "P0.10_3") (pintype "bidirectional"))
      (node (ref "JP4") (pin "2") (pinfunction "2_2") (pintype "passive"))
    )
    (net (code "58") (name "/P0.11") (class "Default")
      (node (ref "IC1") (pin "95") (pinfunction "P0.11_95") (pintype "bidirectional"))
    )
    (net (code "59") (name "/P0.12") (class "Default")
      (node (ref "IC1") (pin "94") (pinfunction "P0.12_94") (pintype "bidirectional"))
    )
    (net (code "60") (name "/P1.0") (class "Default")
      (node (ref "IC1") (pin "79") (pinfunction "P1.0_79") (pintype "bidirectional"))
      (node (ref "R34") (pin "1") (pinfunction "1_1") (pintype "passive"))
      (node (ref "R36") (pin "2") (pinfunction "2_2") (pintype "passive"))
    )
    (net (code "61") (name "/P1.1") (class "Default")
      (node (ref "IC1") (pin "78") (pinfunction "P1.1_78") (pintype "bidirectional"))
      (node (ref "R33") (pin "1") (pinfunction "1_1") (pintype "passive"))
      (node (ref "R35") (pin "2") (pinfunction "2_2") (pintype "passive"))
    )
    (net (code "62") (name "/P1.2") (class "Default")
      (node (ref "IC1") (pin "77") (pinfunction "P1.2_77") (pintype "bidirectional"))
      (node (ref "R32") (pin "1") (pinfunction "1_1") (pintype "passive"))
      (node (ref "R37") (pin "2") (pinfunction "2_2") (pintype "passive"))
    )
    (net (code "63") (name "/P1.3") (class "Default")
      (node (ref "IC1") (pin "76") (pinfunction "P1.3_76") (pintype "bidirectional"))
      (node (ref "R31") (pin "1") (pinfunction "1_1") (pintype "passive"))
      (node (ref "R38") (pin "2") (pinfunction "2_2") (pintype "passive"))
    )
    (net (code "64") (name "/P1.4") (class "Default")
      (node (ref "IC1") (pin "75") (pinfunction "P1.4_75") (pintype "bidirectional"))
    )
    (net (code "65") (name "/P1.5") (class "Default")
      (node (ref "IC1") (pin "74") (pinfunction "P1.5_74") (pintype "bidirectional"))
      (node (ref "SJ2") (pin "1") (pinfunction "1_1") (pintype "passive"))
    )
    (net (code "66") (name "/P1.8") (class "Default")
      (node (ref "IC1") (pin "81") (pinfunction "P1.8_81") (pintype "bidirectional"))
    )
    (net (code "67") (name "/P1.9") (class "Default")
      (node (ref "IC1") (pin "80") (pinfunction "P1.9_80") (pintype "bidirectional"))
    )
    (net (code "68") (name "/P1.10") (class "Default")
      (node (ref "IC1") (pin "73") (pinfunction "P1.10_73") (pintype "bidirectional"))
    )
    (net (code "69") (name "/P1.11") (class "Default")
      (node (ref "IC1") (pin "72") (pinfunction "P1.11_72") (pintype "bidirectional"))
    )
    (net (code "70") (name "/P1.12") (class "Default")
      (node (ref "IC1") (pin "71") (pinfunction "P1.12_71") (pintype "bidirectional"))
    )
    (net (code "71") (name "/P1.13") (class "Default")
      (node (ref "IC1") (pin "70") (pinfunction "P1.13_70") (pintype "bidirectional"))
    )
    (net (code "72") (name "/P1.14") (class "Default")
      (node (ref "IC1") (pin "69") (pinfunction "P1.14_69") (pintype "bidirectional"))
    )
    (net (code "73") (name "/P1.15") (class "Default")
      (node (ref "IC1") (pin "68") (pinfunction "P1.15_68") (pintype "bidirectional"))
      (node (ref "JP3") (pin "3") (pinfunction "3_3") (pintype "passive"))
      (node (ref "U$8") (pin "P5") (pinfunction "SDO_P5") (pintype "bidirectional"))
    )
    (net (code "74") (name "/P2.0") (class "Default")
      (node (ref "IC1") (pin "52") (pinfunction "P2.0_52") (pintype "bidirectional"))
      (node (ref "U$13") (pin "P_1") (pinfunction "P1/EN_P_1") (pintype "bidirectional"))
    )
    (net (code "75") (name "/P2.1") (class "Default")
      (node (ref "IC1") (pin "51") (pinfunction "P2.1_51") (pintype "bidirectional"))
      (node (ref "JP500") (pin "5") (pinfunction "5_5") (pintype "passive"))
    )
    (net (code "76") (name "/P2.2") (class "Default")
      (node (ref "IC1") (pin "50") (pinfunction "P2.2_50") (pintype "bidirectional"))
    )
    (net (code "77") (name "/P2.4") (class "Default")
      (node (ref "IC1") (pin "48") (pinfunction "P2.4_48") (pintype "bidirectional"))
      (node (ref "JP3") (pin "2") (pinfunction "2_2") (pintype "passive"))
      (node (ref "R16") (pin "2") (pinfunction "2_2") (pintype "passive"))
      (node (ref "U$8") (pin "P4") (pinfunction "SCK_P4") (pintype "bidirectional"))
    )
    (net (code "78") (name "/P2.5") (class "Default")
      (node (ref "IC1") (pin "47") (pinfunction "P2.5_47") (pintype "bidirectional"))
      (node (ref "JP3") (pin "1") (pinfunction "1_1") (pintype "passive"))
      (node (ref "R17") (pin "2") (pinfunction "2_2") (pintype "passive"))
      (node (ref "U$8") (pin "P3") (pinfunction "SDI_P3") (pintype "bidirectional"))
    )
    (net (code "79") (name "/P2.6") (class "Default")
      (node (ref "IC1") (pin "54") (pinfunction "P2.6_54") (pintype "bidirectional"))
    )
    (net (code "80") (name "/P2.7") (class "Default")
      (node (ref "IC1") (pin "53") (pinfunction "P2.7_53") (pintype "bidirectional"))
      (node (ref "U$15") (pin "P_1") (pinfunction "P1/EN_P_1") (pintype "bidirectional"))
    )
    (net (code "81") (name "/P2.10") (class "Default")
      (node (ref "IC1") (pin "44") (pinfunction "P2.10_44") (pintype "bidirectional"))
    )
    (net (code "82") (name "/P2.14") (class "Default")
      (node (ref "IC1") (pin "41") (pinfunction "P2.14_41") (pintype "bidirectional"))
    )
    (net (code "83") (name "/P2.15") (class "Default")
      (node (ref "IC1") (pin "40") (pinfunction "P2.15_40") (pintype "bidirectional"))
    )
    (net (code "84") (name "/P3.0") (class "Default")
      (node (ref "IC1") (pin "7") (pinfunction "P3.0_7") (pintype "bidirectional"))
      (node (ref "R22") (pin "2") (pinfunction "2_2") (pintype "passive"))
    )
    (net (code "85") (name "/P3.1") (class "Default")
      (node (ref "IC1") (pin "6") (pinfunction "P3.1_6") (pintype "bidirectional"))
      (node (ref "R23") (pin "2") (pinfunction "2_2") (pintype "passive"))
    )
    (net (code "86") (name "/P3.2") (class "Default")
      (node (ref "IC1") (pin "5") (pinfunction "P3.2_5") (pintype "bidirectional"))
      (node (ref "R21") (pin "2") (pinfunction "2_2") (pintype "passive"))
    )
    (net (code "87") (name "/P3.3") (class "Default")
      (node (ref "IC1") (pin "93") (pinfunction "P3.3_93") (pintype "bidirectional"))
    )
    (net (code "88") (name "/P3.4") (class "Default")
      (node (ref "IC1") (pin "92") (pinfunction "P3.4_92") (pintype "bidirectional"))
    )
    (net (code "89") (name "/P5.0") (class "Default")
      (node (ref "IC1") (pin "58") (pinfunction "P5.0_58") (pintype "bidirectional"))
      (node (ref "IC2") (pin "24") (pinfunction "24_24") (pintype "bidirectional"))
      (node (ref "JP1") (pin "4") (pinfunction "4_4") (pintype "passive"))
      (node (ref "R15") (pin "1") (pinfunction "1_1") (pintype "passive"))
    )
    (net (code "90") (name "/P5.1") (class "Default")
      (node (ref "IC1") (pin "57") (pinfunction "P5.1_57") (pintype "bidirectional"))
      (node (ref "SJ3") (pin "1") (pinfunction "1_1") (pintype "passive"))
    )
    (net (code "91") (name "/P5.2") (class "Default")
      (node (ref "IC1") (pin "56") (pinfunction "P5.2_56") (pintype "bidirectional"))
      (node (ref "IC2") (pin "23") (pinfunction "23_23") (pintype "bidirectional"))
      (node (ref "JP1") (pin "3") (pinfunction "3_3") (pintype "passive"))
      (node (ref "R14") (pin "1") (pinfunction "1_1") (pintype "passive"))
    )
    (net (code "92") (name "/P5.7") (class "Default")
      (node (ref "IC1") (pin "55") (pinfunction "P5.7_55") (pintype "bidirectional"))
    )
    (net (code "93") (name "/P14.0") (class "Default")
      (node (ref "IC1") (pin "31") (pinfunction "P14.0_31") (pintype "bidirectional"))
    )
    (net (code "94") (name "/P14.1") (class "Default")
      (node (ref "IC1") (pin "30") (pinfunction "P14.1_30") (pintype "bidirectional"))
    )
    (net (code "95") (name "/P14.2") (class "Default")
      (node (ref "IC1") (pin "29") (pinfunction "P14.2_29") (pintype "bidirectional"))
    )
    (net (code "96") (name "/P14.3") (class "Default")
      (node (ref "IC1") (pin "28") (pinfunction "P14.3_28") (pintype "bidirectional"))
    )
    (net (code "97") (name "/P14.4") (class "Default")
      (node (ref "IC1") (pin "27") (pinfunction "P14.4_27") (pintype "bidirectional"))
    )
    (net (code "98") (name "/P14.5") (class "Default")
      (node (ref "C29") (pin "1") (pinfunction "1_1") (pintype "passive"))
      (node (ref "IC1") (pin "26") (pinfunction "P14.5_26") (pintype "bidirectional"))
      (node (ref "R13") (pin "2") (pinfunction "2_2") (pintype "passive"))
      (node (ref "R18") (pin "1") (pinfunction "1_1") (pintype "passive"))
    )
    (net (code "99") (name "/P14.6") (class "Default")
      (node (ref "IC1") (pin "25") (pinfunction "P14.6_25") (pintype "bidirectional"))
    )
    (net (code "100") (name "/P14.7") (class "Default")
      (node (ref "C31") (pin "1") (pinfunction "1_1") (pintype "passive"))
      (node (ref "IC1") (pin "24") (pinfunction "P14.7_24") (pintype "bidirectional"))
      (node (ref "R29") (pin "2") (pinfunction "2_2") (pintype "passive"))
      (node (ref "R30") (pin "1") (pinfunction "1_1") (pintype "passive"))
    )
    (net (code "101") (name "/P14.8") (class "Default")
      (node (ref "C30") (pin "1") (pinfunction "1_1") (pintype "passive"))
      (node (ref "IC1") (pin "37") (pinfunction "P14.8_37") (pintype "bidirectional"))
      (node (ref "R19") (pin "1") (pinfunction "1_1") (pintype "passive"))
      (node (ref "R28") (pin "2") (pinfunction "2_2") (pintype "passive"))
    )
    (net (code "102") (name "/P14.9") (class "Default")
      (node (ref "IC1") (pin "36") (pinfunction "P14.9_36") (pintype "bidirectional"))
    )
    (net (code "103") (name "/P14.12") (class "Default")
      (node (ref "IC1") (pin "23") (pinfunction "P14.12_23") (pintype "bidirectional"))
    )
    (net (code "104") (name "/P14.13") (class "Default")
      (node (ref "IC1") (pin "22") (pinfunction "P14.13_22") (pintype "bidirectional"))
    )
    (net (code "105") (name "/P14.14") (class "Default")
      (node (ref "IC1") (pin "21") (pinfunction "P14.14_21") (pintype "bidirectional"))
    )
    (net (code "106") (name "/P14.15") (class "Default")
      (node (ref "IC1") (pin "20") (pinfunction "P14.15_20") (pintype "bidirectional"))
    )
    (net (code "107") (name "/P15.2") (class "Default")
      (node (ref "IC1") (pin "19") (pinfunction "P15.2_19") (pintype "bidirectional"))
    )
    (net (code "108") (name "/P15.3") (class "Default")
      (node (ref "IC1") (pin "18") (pinfunction "P15.3_18") (pintype "bidirectional"))
    )
    (net (code "109") (name "/RESET#") (class "Default")
      (node (ref "C20") (pin "1") (pinfunction "1_1") (pintype "passive"))
      (node (ref "IC1") (pin "65") (pinfunction "PORST#_65") (pintype "bidirectional"))
      (node (ref "JP500") (pin "4") (pinfunction "4_4") (pintype "passive"))
      (node (ref "R1") (pin "1") (pinfunction "1_1") (pintype "passive"))
      (node (ref "SW3") (pin "P") (pinfunction "P_P") (pintype "passive"))
      (node (ref "SW3") (pin "P1") (pinfunction "P_P1") (pintype "passive"))
    )
    (net (code "110") (name "/RTC1") (class "Default")
      (node (ref "IC1") (pin "15") (pinfunction "RTC_XTAL_1_15") (pintype "bidirectional"))
    )
    (net (code "111") (name "/RTC2") (class "Default")
      (node (ref "IC1") (pin "16") (pinfunction "RTC_XTAL_2_16") (pintype "bidirectional"))
    )
    (net (code "112") (name "/TCK") (class "Default")
      (node (ref "IC1") (pin "67") (pinfunction "TCK_67") (pintype "bidirectional"))
      (node (ref "JP500") (pin "3") (pinfunction "3_3") (pintype "passive"))
    )
    (net (code "113") (name "/TMS") (class "Default")
      (node (ref "IC1") (pin "66") (pinfunction "TMS_66") (pintype "bidirectional"))
      (node (ref "JP500") (pin "1") (pinfunction "1_1") (pintype "passive"))
    )
    (net (code "114") (name "/USB_DM") (class "Default")
      (node (ref "IC1") (pin "8") (pinfunction "USB_D-_8") (pintype "bidirectional"))
      (node (ref "JP12") (pin "1") (pinfunction "1_1") (pintype "passive"))
      (node (ref "R10") (pin "2") (pinfunction "2_2") (pintype "passive"))
    )
    (net (code "115") (name "/USB_DP") (class "Default")
      (node (ref "IC1") (pin "9") (pinfunction "USB_D+_9") (pintype "bidirectional"))
      (node (ref "JP13") (pin "1") (pinfunction "1_1") (pintype "passive"))
      (node (ref "R11") (pin "2") (pinfunction "2_2") (pintype "passive"))
    )
    (net (code "116") (name "/VAREF") (class "Default")
      (node (ref "C16") (pin "1") (pinfunction "1_1") (pintype "passive"))
      (node (ref "IC1") (pin "33") (pinfunction "VAREF_33") (pintype "bidirectional"))
      (node (ref "L2") (pin "1") (pinfunction "1_1") (pintype "passive"))
    )
    (net (code "117") (name "/VDDA") (class "Default")
      (node (ref "C17") (pin "1") (pinfunction "1_1") (pintype "passive"))
      (node (ref "IC1") (pin "35") (pinfunction "VDDA_35") (pintype "bidirectional"))
      (node (ref "L3") (pin "1") (pinfunction "1_1") (pintype "passive"))
    )
    (net (code "118") (name "/VDDC") (class "Default")
      (node (ref "C10") (pin "1") (pinfunction "1_1") (pintype "passive"))
      (node (ref "C11") (pin "1") (pinfunction "1_1") (pintype "passive"))
      (node (ref "C7") (pin "1") (pinfunction "1_1") (pintype "passive"))
      (node (ref "C8") (pin "1") (pinfunction "1_1") (pintype "passive"))
      (node (ref "C9") (pin "1") (pinfunction "1_1") (pintype "passive"))
      (node (ref "IC1") (pin "12") (pinfunction "VDDC_12") (pintype "bidirectional"))
      (node (ref "IC1") (pin "42") (pinfunction "VDDC1_42") (pintype "bidirectional"))
      (node (ref "IC1") (pin "64") (pinfunction "VDDC2_64") (pintype "bidirectional"))
      (node (ref "IC1") (pin "86") (pinfunction "VDDC3_86") (pintype "bidirectional"))
    )
    (net (code "119") (name "AGND") (class "Default")
      (node (ref "C16") (pin "2") (pinfunction "2_2") (pintype "passive"))
      (node (ref "C17") (pin "2") (pinfunction "2_2") (pintype "passive"))
      (node (ref "IC1") (pin "32") (pinfunction "VAGND_32") (pintype "bidirectional"))
      (node (ref "IC1") (pin "34") (pinfunction "VSSA_34") (pintype "bidirectional"))
    )
    (net (code "120") (name "GND") (class "Default")
      (node (ref "C1") (pin "2") (pinfunction "2_2") (pintype "passive"))
      (node (ref "C10") (pin "2") (pinfunction "2_2") (pintype "passive"))
      (node (ref "C11") (pin "2") (pinfunction "2_2") (pintype "passive"))
      (node (ref "C12") (pin "2") (pinfunction "2_2") (pintype "passive"))
      (node (ref "C13") (pin "2") (pinfunction "2_2") (pintype "passive"))
      (node (ref "C14") (pin "2") (pinfunction "2_2") (pintype "passive"))
      (node (ref "C15") (pin "1") (pinfunction "1_1") (pintype "passive"))
      (node (ref "C18") (pin "1") (pinfunction "1_1") (pintype "passive"))
      (node (ref "C19") (pin "1") (pinfunction "1_1") (pintype "passive"))
      (node (ref "C2") (pin "2") (pinfunction "2_2") (pintype "passive"))
      (node (ref "C20") (pin "2") (pinfunction "2_2") (pintype "passive"))
      (node (ref "C21") (pin "1") (pinfunction "1_1") (pintype "passive"))
      (node (ref "C22") (pin "2") (pinfunction "2_2") (pintype "passive"))
      (node (ref "C23") (pin "2") (pinfunction "2_2") (pintype "passive"))
      (node (ref "C24") (pin "2") (pinfunction "2_2") (pintype "passive"))
      (node (ref "C25") (pin "2") (pinfunction "2_2") (pintype "passive"))
      (node (ref "C26") (pin "2") (pinfunction "2_2") (pintype "passive"))
      (node (ref "C27") (pin "2") (pinfunction "2_2") (pintype "passive"))
      (node (ref "C28") (pin "1") (pinfunction "1_1") (pintype "passive"))
      (node (ref "C29") (pin "2") (pinfunction "2_2") (pintype "passive"))
      (node (ref "C3") (pin "2") (pinfunction "2_2") (pintype "passive"))
      (node (ref "C30") (pin "2") (pinfunction "2_2") (pintype "passive"))
      (node (ref "C31") (pin "2") (pinfunction "2_2") (pintype "passive"))
      (node (ref "C4") (pin "2") (pinfunction "2_2") (pintype "passive"))
      (node (ref "C5") (pin "2") (pinfunction "2_2") (pintype "passive"))
      (node (ref "C6") (pin "2") (pinfunction "2_2") (pintype "passive"))
      (node (ref "C7") (pin "2") (pinfunction "2_2") (pintype "passive"))
      (node (ref "C8") (pin "2") (pinfunction "2_2") (pintype "passive"))
      (node (ref "C9") (pin "2") (pinfunction "2_2") (pintype "passive"))
      (node (ref "D1") (pin "3") (pinfunction "3_3") (pintype "passive"))
      (node (ref "IC1") (pin "59") (pinfunction "VSS_59") (pintype "bidirectional"))
      (node (ref "IC1") (pin "63") (pinfunction "VSSO_63") (pintype "bidirectional"))
      (node (ref "IC1") (pin "EXP") (pinfunction "EPAD_EXP") (pintype "bidirectional"))
      (node (ref "IC2") (pin "18") (pinfunction "18_18") (pintype "bidirectional"))
      (node (ref "IC2") (pin "20") (pinfunction "20_20") (pintype "bidirectional"))
      (node (ref "JP1") (pin "2") (pinfunction "2_2") (pintype "passive"))
      (node (ref "JP2") (pin "3") (pinfunction "3_3") (pintype "passive"))
      (node (ref "JP500") (pin "6") (pinfunction "6_6") (pintype "passive"))
      (node (ref "JP6") (pin "2") (pinfunction "2_2") (pintype "passive"))
      (node (ref "JP7") (pin "1") (pinfunction "1_1") (pintype "passive"))
      (node (ref "JP7") (pin "2") (pinfunction "2_2") (pintype "passive"))
      (node (ref "LED1") (pin "C") (pinfunction "C_C") (pintype "passive"))
      (node (ref "LED2") (pin "C") (pinfunction "C_C") (pintype "passive"))
      (node (ref "LED3") (pin "C") (pinfunction "C_C") (pintype "passive"))
      (node (ref "LED4") (pin "C") (pinfunction "C_C") (pintype "passive"))
      (node (ref "LED5") (pin "C") (pinfunction "C_C") (pintype "passive"))
      (node (ref "LED6") (pin "C") (pinfunction "C_C") (pintype "passive"))
      (node (ref "M1/DY") (pin "1") (pinfunction "1_1") (pintype "passive"))
      (node (ref "M1/DY") (pin "2") (pinfunction "2_2") (pintype "passive"))
      (node (ref "M1/MOTOR") (pin "7") (pinfunction "7_7") (pintype "passive"))
      (node (ref "M1/MOTOR") (pin "8") (pinfunction "8_8") (pintype "passive"))
      (node (ref "M2/DY") (pin "1") (pinfunction "1_1") (pintype "passive"))
      (node (ref "M2/DY") (pin "2") (pinfunction "2_2") (pintype "passive"))
      (node (ref "M2/MOTOR") (pin "7") (pinfunction "7_7") (pintype "passive"))
      (node (ref "M2/MOTOR") (pin "8") (pinfunction "8_8") (pintype "passive"))
      (node (ref "M3/DY") (pin "1") (pinfunction "1_1") (pintype "passive"))
      (node (ref "M3/DY") (pin "2") (pinfunction "2_2") (pintype "passive"))
      (node (ref "M3/MOTOR") (pin "7") (pinfunction "7_7") (pintype "passive"))
      (node (ref "M3/MOTOR") (pin "8") (pinfunction "8_8") (pintype "passive"))
      (node (ref "M4/DY") (pin "1") (pinfunction "1_1") (pintype "passive"))
      (node (ref "M4/DY") (pin "2") (pinfunction "2_2") (pintype "passive"))
      (node (ref "M4/MOTOR") (pin "7") (pinfunction "7_7") (pintype "passive"))
      (node (ref "M4/MOTOR") (pin "8") (pinfunction "8_8") (pintype "passive"))
      (node (ref "R18") (pin "2") (pinfunction "2_2") (pintype "passive"))
      (node (ref "R19") (pin "2") (pinfunction "2_2") (pintype "passive"))
      (node (ref "R24") (pin "2") (pinfunction "2_2") (pintype "passive"))
      (node (ref "R25") (pin "2") (pinfunction "2_2") (pintype "passive"))
      (node (ref "R26") (pin "2") (pinfunction "2_2") (pintype "passive"))
      (node (ref "R27") (pin "2") (pinfunction "2_2") (pintype "passive"))
      (node (ref "R30") (pin "2") (pinfunction "2_2") (pintype "passive"))
      (node (ref "R7") (pin "2") (pinfunction "2_2") (pintype "passive"))
      (node (ref "RC") (pin "2") (pinfunction "2_2") (pintype "passive"))
      (node (ref "SW3") (pin "S") (pinfunction "S_S") (pintype "passive"))
      (node (ref "SW3") (pin "S1") (pinfunction "S_S1") (pintype "passive"))
      (node (ref "TO3.3V") (pin "1") (pinfunction "ADJ_1") (pintype "power_in"))
      (node (ref "U$11") (pin "A1") (pinfunction "A1/VSS_A1") (pintype "bidirectional"))
      (node (ref "U$11") (pin "A2") (pinfunction "A2/VSS_A2") (pintype "bidirectional"))
      (node (ref "U$11") (pin "C1") (pinfunction "C1/VSS_C1") (pintype "bidirectional"))
      (node (ref "U$13") (pin "P_4") (pinfunction "P4/GND_P_4") (pintype "bidirectional"))
      (node (ref "U$15") (pin "P_4") (pinfunction "P4/GND_P_4") (pintype "bidirectional"))
      (node (ref "U$16") (pin "P12_GND") (pinfunction "P12_GND_P12_GND") (pintype "bidirectional"))
      (node (ref "U$18") (pin "P_4") (pinfunction "P4/GND_P_4") (pintype "bidirectional"))
      (node (ref "U$20") (pin "P_4") (pinfunction "P4/GND_P_4") (pintype "bidirectional"))
      (node (ref "U$22") (pin "P$1") (pinfunction "P$1_P$1") (pintype "bidirectional"))
      (node (ref "U$7") (pin "1") (pinfunction "GND_1") (pintype "bidirectional"))
      (node (ref "U$8") (pin "P1") (pinfunction "GND1_P1") (pintype "bidirectional"))
      (node (ref "U$8") (pin "P7") (pinfunction "GND2_P7") (pintype "bidirectional"))
      (node (ref "U$9") (pin "P$1") (pinfunction "P$1_P$1") (pintype "bidirectional"))
      (node (ref "X3") (pin "5") (pinfunction "5_5") (pintype "passive"))
    )
    (net (code "121") (name "Net-(C19-Pad2)") (class "Default")
      (node (ref "C19") (pin "2") (pinfunction "2_2") (pintype "passive"))
      (node (ref "IC2") (pin "10") (pinfunction "10_10") (pintype "bidirectional"))
    )
    (net (code "122") (name "Net-(D1-Pad1)") (class "Default")
      (node (ref "D1") (pin "1") (pinfunction "1_1") (pintype "passive"))
      (node (ref "R11") (pin "1") (pinfunction "1_1") (pintype "passive"))
      (node (ref "X3") (pin "3") (pinfunction "3_3") (pintype "passive"))
    )
    (net (code "123") (name "Net-(D1-Pad2)") (class "Default")
      (node (ref "D1") (pin "2") (pinfunction "2_2") (pintype "passive"))
      (node (ref "R10") (pin "1") (pinfunction "1_1") (pintype "passive"))
      (node (ref "X3") (pin "2") (pinfunction "2_2") (pintype "passive"))
    )
    (net (code "124") (name "Net-(IC1-VBUS)") (class "Default")
      (node (ref "D2") (pin "A") (pinfunction "A_A") (pintype "passive"))
      (node (ref "IC1") (pin "10") (pinfunction "VBUS_10") (pintype "bidirectional"))
      (node (ref "JP14") (pin "1") (pinfunction "1_1") (pintype "passive"))
      (node (ref "L1") (pin "1") (pinfunction "1_1") (pintype "passive"))
    )
    (net (code "125") (name "Net-(IC1-XTAL1)") (class "Default")
      (node (ref "C12") (pin "1") (pinfunction "1_1") (pintype "passive"))
      (node (ref "IC1") (pin "61") (pinfunction "XTAL1_61") (pintype "bidirectional"))
      (node (ref "Q1") (pin "1") (pinfunction "1_1") (pintype "passive"))
    )
    (net (code "126") (name "Net-(IC1-XTAL2)") (class "Default")
      (node (ref "IC1") (pin "62") (pinfunction "XTAL2_62") (pintype "bidirectional"))
      (node (ref "R12") (pin "1") (pinfunction "1_1") (pintype "passive"))
    )
    (net (code "127") (name "Net-(JP2-Pad2)") (class "Default")
      (node (ref "JP2") (pin "2") (pinfunction "2_2") (pintype "passive"))
      (node (ref "R8") (pin "2") (pinfunction "2_2") (pintype "passive"))
      (node (ref "SJ2") (pin "2") (pinfunction "2_2") (pintype "passive"))
      (node (ref "U$16") (pin "P14_TX") (pinfunction "P14_TX_P14_TX") (pintype "bidirectional"))
    )
    (net (code "128") (name "Net-(JP2-Pad4)") (class "Default")
      (node (ref "JP2") (pin "4") (pinfunction "4_4") (pintype "passive"))
      (node (ref "R9") (pin "2") (pinfunction "2_2") (pintype "passive"))
      (node (ref "SJ3") (pin "2") (pinfunction "2_2") (pintype "passive"))
      (node (ref "U$16") (pin "P13_RX") (pinfunction "P13_RX_P13_RX") (pintype "bidirectional"))
    )
    (net (code "129") (name "Net-(JP4-Pad1)") (class "Default")
      (node (ref "JP4") (pin "1") (pinfunction "1_1") (pintype "passive"))
      (node (ref "R3") (pin "2") (pinfunction "2_2") (pintype "passive"))
      (node (ref "R4") (pin "2") (pinfunction "2_2") (pintype "passive"))
      (node (ref "R7") (pin "1") (pinfunction "1_1") (pintype "passive"))
      (node (ref "U$22") (pin "P$2") (pinfunction "P$2_P$2") (pintype "bidirectional"))
    )
    (net (code "130") (name "Net-(JP15-Pad1)") (class "Default")
      (node (ref "JP15") (pin "1") (pinfunction "1_1") (pintype "passive"))
      (node (ref "M1/MOTOR") (pin "5") (pinfunction "5_5") (pintype "passive"))
      (node (ref "M1/MOTOR") (pin "6") (pinfunction "6_6") (pintype "passive"))
    )
    (net (code "131") (name "Net-(JP15-Pad2)") (class "Default")
      (node (ref "JP15") (pin "2") (pinfunction "2_2") (pintype "passive"))
      (node (ref "M1/MOTOR") (pin "3") (pinfunction "3_3") (pintype "passive"))
      (node (ref "M1/MOTOR") (pin "4") (pinfunction "4_4") (pintype "passive"))
    )
    (net (code "132") (name "Net-(JP15-Pad3)") (class "Default")
      (node (ref "JP15") (pin "3") (pinfunction "3_3") (pintype "passive"))
      (node (ref "M1/MOTOR") (pin "1") (pinfunction "1_1") (pintype "passive"))
      (node (ref "M1/MOTOR") (pin "2") (pinfunction "2_2") (pintype "passive"))
    )
    (net (code "133") (name "Net-(JP16-Pad1)") (class "Default")
      (node (ref "JP16") (pin "1") (pinfunction "1_1") (pintype "passive"))
      (node (ref "M2/MOTOR") (pin "5") (pinfunction "5_5") (pintype "passive"))
      (node (ref "M2/MOTOR") (pin "6") (pinfunction "6_6") (pintype "passive"))
    )
    (net (code "134") (name "Net-(JP16-Pad2)") (class "Default")
      (node (ref "JP16") (pin "2") (pinfunction "2_2") (pintype "passive"))
      (node (ref "M2/MOTOR") (pin "3") (pinfunction "3_3") (pintype "passive"))
      (node (ref "M2/MOTOR") (pin "4") (pinfunction "4_4") (pintype "passive"))
    )
    (net (code "135") (name "Net-(JP16-Pad3)") (class "Default")
      (node (ref "JP16") (pin "3") (pinfunction "3_3") (pintype "passive"))
      (node (ref "M2/MOTOR") (pin "1") (pinfunction "1_1") (pintype "passive"))
      (node (ref "M2/MOTOR") (pin "2") (pinfunction "2_2") (pintype "passive"))
    )
    (net (code "136") (name "Net-(JP17-Pad1)") (class "Default")
      (node (ref "JP17") (pin "1") (pinfunction "1_1") (pintype "passive"))
      (node (ref "M3/MOTOR") (pin "5") (pinfunction "5_5") (pintype "passive"))
      (node (ref "M3/MOTOR") (pin "6") (pinfunction "6_6") (pintype "passive"))
    )
    (net (code "137") (name "Net-(JP17-Pad2)") (class "Default")
      (node (ref "JP17") (pin "2") (pinfunction "2_2") (pintype "passive"))
      (node (ref "M3/MOTOR") (pin "3") (pinfunction "3_3") (pintype "passive"))
      (node (ref "M3/MOTOR") (pin "4") (pinfunction "4_4") (pintype "passive"))
    )
    (net (code "138") (name "Net-(JP17-Pad3)") (class "Default")
      (node (ref "JP17") (pin "3") (pinfunction "3_3") (pintype "passive"))
      (node (ref "M3/MOTOR") (pin "1") (pinfunction "1_1") (pintype "passive"))
      (node (ref "M3/MOTOR") (pin "2") (pinfunction "2_2") (pintype "passive"))
    )
    (net (code "139") (name "Net-(JP18-Pad1)") (class "Default")
      (node (ref "JP18") (pin "1") (pinfunction "1_1") (pintype "passive"))
      (node (ref "M4/MOTOR") (pin "5") (pinfunction "5_5") (pintype "passive"))
      (node (ref "M4/MOTOR") (pin "6") (pinfunction "6_6") (pintype "passive"))
    )
    (net (code "140") (name "Net-(JP18-Pad2)") (class "Default")
      (node (ref "JP18") (pin "2") (pinfunction "2_2") (pintype "passive"))
      (node (ref "M4/MOTOR") (pin "3") (pinfunction "3_3") (pintype "passive"))
      (node (ref "M4/MOTOR") (pin "4") (pinfunction "4_4") (pintype "passive"))
    )
    (net (code "141") (name "Net-(JP18-Pad3)") (class "Default")
      (node (ref "JP18") (pin "3") (pinfunction "3_3") (pintype "passive"))
      (node (ref "M4/MOTOR") (pin "1") (pinfunction "1_1") (pintype "passive"))
      (node (ref "M4/MOTOR") (pin "2") (pinfunction "2_2") (pintype "passive"))
    )
    (net (code "142") (name "Net-(JP19-Pad1)") (class "Default")
      (node (ref "JP19") (pin "1") (pinfunction "1_1") (pintype "passive"))
      (node (ref "R13") (pin "1") (pinfunction "1_1") (pintype "passive"))
    )
    (net (code "143") (name "Net-(JP19-Pad2)") (class "Default")
      (node (ref "JP19") (pin "2") (pinfunction "2_2") (pintype "passive"))
      (node (ref "R28") (pin "1") (pinfunction "1_1") (pintype "passive"))
    )
    (net (code "144") (name "Net-(JP19-Pad3)") (class "Default")
      (node (ref "JP19") (pin "3") (pinfunction "3_3") (pintype "passive"))
      (node (ref "R29") (pin "1") (pinfunction "1_1") (pintype "passive"))
    )
    (net (code "145") (name "Net-(L1-Pad2)") (class "Default")
      (node (ref "L1") (pin "2") (pinfunction "2_2") (pintype "passive"))
      (node (ref "X3") (pin "1") (pinfunction "1_1") (pintype "passive"))
    )
    (net (code "146") (name "Net-(LED1-PadA)") (class "Default")
      (node (ref "LED1") (pin "A") (pinfunction "A_A") (pintype "passive"))
      (node (ref "R6") (pin "1") (pinfunction "1_1") (pintype "passive"))
    )
    (net (code "147") (name "Net-(LED2-PadA)") (class "Default")
      (node (ref "LED2") (pin "A") (pinfunction "A_A") (pintype "passive"))
      (node (ref "R20") (pin "1") (pinfunction "1_1") (pintype "passive"))
    )
    (net (code "148") (name "Net-(LED3-PadA)") (class "Default")
      (node (ref "LED3") (pin "A") (pinfunction "A_A") (pintype "passive"))
      (node (ref "R21") (pin "1") (pinfunction "1_1") (pintype "passive"))
    )
    (net (code "149") (name "Net-(LED4-PadA)") (class "Default")
      (node (ref "LED4") (pin "A") (pinfunction "A_A") (pintype "passive"))
      (node (ref "R22") (pin "1") (pinfunction "1_1") (pintype "passive"))
    )
    (net (code "150") (name "Net-(LED5-PadA)") (class "Default")
      (node (ref "LED5") (pin "A") (pinfunction "A_A") (pintype "passive"))
      (node (ref "R23") (pin "1") (pinfunction "1_1") (pintype "passive"))
    )
    (net (code "151") (name "Net-(LED6-PadA)") (class "Default")
      (node (ref "LED6") (pin "A") (pinfunction "A_A") (pintype "passive"))
      (node (ref "R5") (pin "1") (pinfunction "1_1") (pintype "passive"))
    )
    (net (code "152") (name "Net-(M1/DY-Pad6)") (class "Default")
      (node (ref "M1/DY") (pin "6") (pinfunction "6_6") (pintype "passive"))
      (node (ref "M2/DY") (pin "5") (pinfunction "5_5") (pintype "passive"))
      (node (ref "R35") (pin "1") (pinfunction "1_1") (pintype "passive"))
    )
    (net (code "153") (name "Net-(M2/DY-Pad6)") (class "Default")
      (node (ref "M2/DY") (pin "6") (pinfunction "6_6") (pintype "passive"))
      (node (ref "M3/DY") (pin "5") (pinfunction "5_5") (pintype "passive"))
      (node (ref "R37") (pin "1") (pinfunction "1_1") (pintype "passive"))
    )
    (net (code "154") (name "Net-(M3/DY-Pad6)") (class "Default")
      (node (ref "M3/DY") (pin "6") (pinfunction "6_6") (pintype "passive"))
      (node (ref "M4/DY") (pin "5") (pinfunction "5_5") (pintype "passive"))
      (node (ref "R38") (pin "1") (pinfunction "1_1") (pintype "passive"))
    )
    (net (code "155") (name "Net-(Q1-2)") (class "Default")
      (node (ref "C13") (pin "1") (pinfunction "1_1") (pintype "passive"))
      (node (ref "Q1") (pin "3") (pinfunction "2_3") (pintype "passive"))
      (node (ref "R12") (pin "2") (pinfunction "2_2") (pintype "passive"))
    )
    (net (code "156") (name "Net-(R2-Pad1)") (class "Default")
      (node (ref "R2") (pin "1") (pinfunction "1_1") (pintype "passive"))
      (node (ref "SJ1") (pin "1") (pinfunction "1_1") (pintype "passive"))
      (node (ref "U$9") (pin "P$2") (pinfunction "P$2_P$2") (pintype "bidirectional"))
    )
    (net (code "157") (name "Net-(U$11-B2{slash}VDD)") (class "Default")
      (node (ref "C28") (pin "2") (pinfunction "2_2") (pintype "passive"))
      (node (ref "R2") (pin "2") (pinfunction "2_2") (pintype "passive"))
      (node (ref "U$11") (pin "B2") (pinfunction "B2/VDD_B2") (pintype "bidirectional"))
    )
    (net (code "158") (name "Net-(U$11-C2{slash}BIF)") (class "Default")
      (node (ref "R3") (pin "1") (pinfunction "1_1") (pintype "passive"))
      (node (ref "U$11") (pin "C2") (pinfunction "C2/BIF_C2") (pintype "bidirectional"))
    )
    (net (code "159") (name "Net-(U$13-P2{slash}OUT)") (class "Default")
      (node (ref "JP8") (pin "2") (pinfunction "2_2") (pintype "passive"))
      (node (ref "U$13") (pin "P_2") (pinfunction "P2/OUT_P_2") (pintype "bidirectional"))
      (node (ref "U$13") (pin "P_3") (pinfunction "P3/OUT_P_3") (pintype "bidirectional"))
      (node (ref "U$13") (pin "P_5") (pinfunction "P5/OUT_P_5") (pintype "bidirectional"))
    )
    (net (code "160") (name "Net-(U$13-P6{slash}REXT)") (class "Default")
      (node (ref "R24") (pin "1") (pinfunction "1_1") (pintype "passive"))
      (node (ref "U$13") (pin "P_6") (pinfunction "P6/REXT_P_6") (pintype "bidirectional"))
    )
    (net (code "161") (name "Net-(U$15-P2{slash}OUT)") (class "Default")
      (node (ref "JP9") (pin "2") (pinfunction "2_2") (pintype "passive"))
      (node (ref "U$15") (pin "P_2") (pinfunction "P2/OUT_P_2") (pintype "bidirectional"))
      (node (ref "U$15") (pin "P_3") (pinfunction "P3/OUT_P_3") (pintype "bidirectional"))
      (node (ref "U$15") (pin "P_5") (pinfunction "P5/OUT_P_5") (pintype "bidirectional"))
    )
    (net (code "162") (name "Net-(U$15-P6{slash}REXT)") (class "Default")
      (node (ref "R25") (pin "1") (pinfunction "1_1") (pintype "passive"))
      (node (ref "U$15") (pin "P_6") (pinfunction "P6/REXT_P_6") (pintype "bidirectional"))
    )
    (net (code "163") (name "Net-(U$16-P19_STATUS)") (class "Default")
      (node (ref "R6") (pin "2") (pinfunction "2_2") (pintype "passive"))
      (node (ref "U$16") (pin "PIO2") (pinfunction "P19_STATUS_PIO2") (pintype "bidirectional"))
    )
    (net (code "164") (name "Net-(U$18-P2{slash}OUT)") (class "Default")
      (node (ref "JP10") (pin "2") (pinfunction "2_2") (pintype "passive"))
      (node (ref "U$18") (pin "P_2") (pinfunction "P2/OUT_P_2") (pintype "bidirectional"))
      (node (ref "U$18") (pin "P_3") (pinfunction "P3/OUT_P_3") (pintype "bidirectional"))
      (node (ref "U$18") (pin "P_5") (pinfunction "P5/OUT_P_5") (pintype "bidirectional"))
    )
    (net (code "165") (name "Net-(U$18-P6{slash}REXT)") (class "Default")
      (node (ref "R26") (pin "1") (pinfunction "1_1") (pintype "passive"))
      (node (ref "U$18") (pin "P_6") (pinfunction "P6/REXT_P_6") (pintype "bidirectional"))
    )
    (net (code "166") (name "Net-(U$20-P2{slash}OUT)") (class "Default")
      (node (ref "JP11") (pin "2") (pinfunction "2_2") (pintype "passive"))
      (node (ref "U$20") (pin "P_2") (pinfunction "P2/OUT_P_2") (pintype "bidirectional"))
      (node (ref "U$20") (pin "P_3") (pinfunction "P3/OUT_P_3") (pintype "bidirectional"))
      (node (ref "U$20") (pin "P_5") (pinfunction "P5/OUT_P_5") (pintype "bidirectional"))
    )
    (net (code "167") (name "Net-(U$20-P6{slash}REXT)") (class "Default")
      (node (ref "R27") (pin "1") (pinfunction "1_1") (pintype "passive"))
      (node (ref "U$20") (pin "P_6") (pinfunction "P6/REXT_P_6") (pintype "bidirectional"))
    )
    (net (code "168") (name "VDD3.3") (class "Default")
      (node (ref "C1") (pin "1") (pinfunction "1_1") (pintype "passive"))
      (node (ref "C14") (pin "1") (pinfunction "1_1") (pintype "passive"))
      (node (ref "C15") (pin "2") (pinfunction "2_2") (pintype "passive"))
      (node (ref "C18") (pin "2") (pinfunction "2_2") (pintype "passive"))
      (node (ref "C2") (pin "1") (pinfunction "1_1") (pintype "passive"))
      (node (ref "C21") (pin "2") (pinfunction "2_2") (pintype "passive"))
      (node (ref "C23") (pin "1") (pinfunction "1_1") (pintype "passive"))
      (node (ref "C3") (pin "1") (pinfunction "1_1") (pintype "passive"))
      (node (ref "C4") (pin "1") (pinfunction "1_1") (pintype "passive"))
      (node (ref "C5") (pin "1") (pinfunction "1_1") (pintype "passive"))
      (node (ref "C6") (pin "1") (pinfunction "1_1") (pintype "passive"))
      (node (ref "IC1") (pin "11") (pinfunction "VDDP_11") (pintype "bidirectional"))
      (node (ref "IC1") (pin "17") (pinfunction "VBAT_17") (pintype "bidirectional"))
      (node (ref "IC1") (pin "43") (pinfunction "VDDP1_43") (pintype "bidirectional"))
      (node (ref "IC1") (pin "60") (pinfunction "VDDP2_60") (pintype "bidirectional"))
      (node (ref "IC1") (pin "87") (pinfunction "VDDP3_87") (pintype "bidirectional"))
      (node (ref "IC2") (pin "13") (pinfunction "13_13") (pintype "bidirectional"))
      (node (ref "IC2") (pin "22") (pinfunction "22_22") (pintype "bidirectional"))
      (node (ref "IC2") (pin "8") (pinfunction "8_8") (pintype "bidirectional"))
      (node (ref "JP1") (pin "1") (pinfunction "1_1") (pintype "passive"))
      (node (ref "JP10") (pin "1") (pinfunction "1_1") (pintype "passive"))
      (node (ref "JP11") (pin "1") (pinfunction "1_1") (pintype "passive"))
      (node (ref "JP2") (pin "1") (pinfunction "1_1") (pintype "passive"))
      (node (ref "JP20") (pin "1") (pinfunction "1_1") (pintype "passive"))
      (node (ref "JP20") (pin "2") (pinfunction "2_2") (pintype "passive"))
      (node (ref "JP21") (pin "1") (pinfunction "1_1") (pintype "passive"))
      (node (ref "JP21") (pin "2") (pinfunction "2_2") (pintype "passive"))
      (node (ref "JP22") (pin "1") (pinfunction "1_1") (pintype "passive"))
      (node (ref "JP22") (pin "2") (pinfunction "2_2") (pintype "passive"))
      (node (ref "JP23") (pin "1") (pinfunction "1_1") (pintype "passive"))
      (node (ref "JP23") (pin "2") (pinfunction "2_2") (pintype "passive"))
      (node (ref "JP500") (pin "2") (pinfunction "2_2") (pintype "passive"))
      (node (ref "JP6") (pin "1") (pinfunction "1_1") (pintype "passive"))
      (node (ref "JP8") (pin "1") (pinfunction "1_1") (pintype "passive"))
      (node (ref "JP9") (pin "1") (pinfunction "1_1") (pintype "passive"))
      (node (ref "L2") (pin "2") (pinfunction "2_2") (pintype "passive"))
      (node (ref "L3") (pin "2") (pinfunction "2_2") (pintype "passive"))
      (node (ref "R1") (pin "2") (pinfunction "2_2") (pintype "passive"))
      (node (ref "R14") (pin "2") (pinfunction "2_2") (pintype "passive"))
      (node (ref "R15") (pin "2") (pinfunction "2_2") (pintype "passive"))
      (node (ref "R16") (pin "1") (pinfunction "1_1") (pintype "passive"))
      (node (ref "R17") (pin "1") (pinfunction "1_1") (pintype "passive"))
      (node (ref "R4") (pin "1") (pinfunction "1_1") (pintype "passive"))
      (node (ref "R5") (pin "2") (pinfunction "2_2") (pintype "passive"))
      (node (ref "R8") (pin "1") (pinfunction "1_1") (pintype "passive"))
      (node (ref "R9") (pin "1") (pinfunction "1_1") (pintype "passive"))
      (node (ref "RC") (pin "1") (pinfunction "1_1") (pintype "passive"))
      (node (ref "SJ1") (pin "2") (pinfunction "2_2") (pintype "passive"))
      (node (ref "TO3.3V") (pin "2") (pinfunction "OUT1_2") (pintype "power_in"))
      (node (ref "TO3.3V") (pin "4") (pinfunction "OUT2_4") (pintype "power_in"))
      (node (ref "U$16") (pin "P11_VDD") (pinfunction "P11_VDD_P11_VDD") (pintype "bidirectional"))
      (node (ref "U$8") (pin "P6") (pinfunction "VDDIO_P6") (pintype "bidirectional"))
      (node (ref "U$8") (pin "P8") (pinfunction "VDD_P8") (pintype "bidirectional"))
    )
    (net (code "169") (name "VDD5") (class "Default")
      (node (ref "C22") (pin "1") (pinfunction "1_1") (pintype "passive"))
      (node (ref "C24") (pin "1") (pinfunction "1_1") (pintype "passive"))
      (node (ref "C26") (pin "1") (pinfunction "1_1") (pintype "passive"))
      (node (ref "D2") (pin "C") (pinfunction "C_C") (pintype "passive"))
      (node (ref "JP5") (pin "1") (pinfunction "1_1") (pintype "passive"))
      (node (ref "M1/DY") (pin "3") (pinfunction "3_3") (pintype "passive"))
      (node (ref "M1/DY") (pin "4") (pinfunction "4_4") (pintype "passive"))
      (node (ref "M2/DY") (pin "3") (pinfunction "3_3") (pintype "passive"))
      (node (ref "M2/DY") (pin "4") (pinfunction "4_4") (pintype "passive"))
      (node (ref "M3/DY") (pin "3") (pinfunction "3_3") (pintype "passive"))
      (node (ref "M3/DY") (pin "4") (pinfunction "4_4") (pintype "passive"))
      (node (ref "M4/DY") (pin "3") (pinfunction "3_3") (pintype "passive"))
      (node (ref "M4/DY") (pin "4") (pinfunction "4_4") (pintype "passive"))
      (node (ref "R31") (pin "2") (pinfunction "2_2") (pintype "passive"))
      (node (ref "R32") (pin "2") (pinfunction "2_2") (pintype "passive"))
      (node (ref "R33") (pin "2") (pinfunction "2_2") (pintype "passive"))
      (node (ref "R34") (pin "2") (pinfunction "2_2") (pintype "passive"))
      (node (ref "TO3.3V") (pin "3") (pinfunction "IN_3") (pintype "power_in"))
      (node (ref "U$7") (pin "2") (pinfunction "OUT/5V_2") (pintype "bidirectional"))
    )
    (net (code "170") (name "unconnected-(IC2-Pad1)") (class "Default")
      (node (ref "IC2") (pin "1") (pinfunction "1_1") (pintype "bidirectional"))
    )
    (net (code "171") (name "unconnected-(IC2-Pad2)") (class "Default")
      (node (ref "IC2") (pin "2") (pinfunction "2_2") (pintype "bidirectional"))
    )
    (net (code "172") (name "unconnected-(IC2-Pad3)") (class "Default")
      (node (ref "IC2") (pin "3") (pinfunction "3_3") (pintype "bidirectional"))
    )
    (net (code "173") (name "unconnected-(IC2-Pad4)") (class "Default")
      (node (ref "IC2") (pin "4") (pinfunction "4_4") (pintype "bidirectional"))
    )
    (net (code "174") (name "unconnected-(IC2-Pad5)") (class "Default")
      (node (ref "IC2") (pin "5") (pinfunction "5_5") (pintype "bidirectional"))
    )
    (net (code "175") (name "unconnected-(IC2-Pad6)") (class "Default")
      (node (ref "IC2") (pin "6") (pinfunction "6_6") (pintype "bidirectional"))
    )
    (net (code "176") (name "unconnected-(IC2-Pad7)") (class "Default")
      (node (ref "IC2") (pin "7") (pinfunction "7_7") (pintype "bidirectional"))
    )
    (net (code "177") (name "unconnected-(IC2-Pad9)") (class "Default")
      (node (ref "IC2") (pin "9") (pinfunction "9_9") (pintype "bidirectional"))
    )
    (net (code "178") (name "unconnected-(IC2-Pad11)") (class "Default")
      (node (ref "IC2") (pin "11") (pinfunction "11_11") (pintype "bidirectional"))
    )
    (net (code "179") (name "unconnected-(IC2-Pad14)") (class "Default")
      (node (ref "IC2") (pin "14") (pinfunction "14_14") (pintype "bidirectional"))
    )
    (net (code "180") (name "unconnected-(IC2-Pad15)") (class "Default")
      (node (ref "IC2") (pin "15") (pinfunction "15_15") (pintype "bidirectional"))
    )
    (net (code "181") (name "unconnected-(IC2-Pad16)") (class "Default")
      (node (ref "IC2") (pin "16") (pinfunction "16_16") (pintype "bidirectional"))
    )
    (net (code "182") (name "unconnected-(IC2-Pad17)") (class "Default")
      (node (ref "IC2") (pin "17") (pinfunction "17_17") (pintype "bidirectional"))
    )
    (net (code "183") (name "unconnected-(IC2-Pad19)") (class "Default")
      (node (ref "IC2") (pin "19") (pinfunction "19_19") (pintype "bidirectional"))
    )
    (net (code "184") (name "unconnected-(IC2-Pad21)") (class "Default")
      (node (ref "IC2") (pin "21") (pinfunction "21_21") (pintype "bidirectional"))
    )
    (net (code "185") (name "unconnected-(U$8-CSB-PadP2)") (class "Default")
      (node (ref "U$8") (pin "P2") (pinfunction "CSB_P2") (pintype "bidirectional"))
    )
    (net (code "186") (name "unconnected-(X3-Pad4)") (class "Default")
      (node (ref "X3") (pin "4") (pinfunction "4_4") (pintype "passive"))
    )
    (net (code "187") (name "unconnected-(X3-PadS1)") (class "Default")
      (node (ref "X3") (pin "S1") (pinfunction "S1_S1") (pintype "passive"))
    )
    (net (code "188") (name "unconnected-(X3-PadS2)") (class "Default")
      (node (ref "X3") (pin "S2") (pinfunction "S2_S2") (pintype "passive"))
    )
    (net (code "189") (name "unconnected-(X3-PadS3)") (class "Default")
      (node (ref "X3") (pin "S3") (pinfunction "S3_S3") (pintype "passive"))
    )
    (net (code "190") (name "unconnected-(X3-PadS4)") (class "Default")
      (node (ref "X3") (pin "S4") (pinfunction "S4_S4") (pintype "passive"))
    )
  )
)
